# MT-CHARHER_V1_0_0.net
KiCad netlist of a schematic drawn in Altium Designer
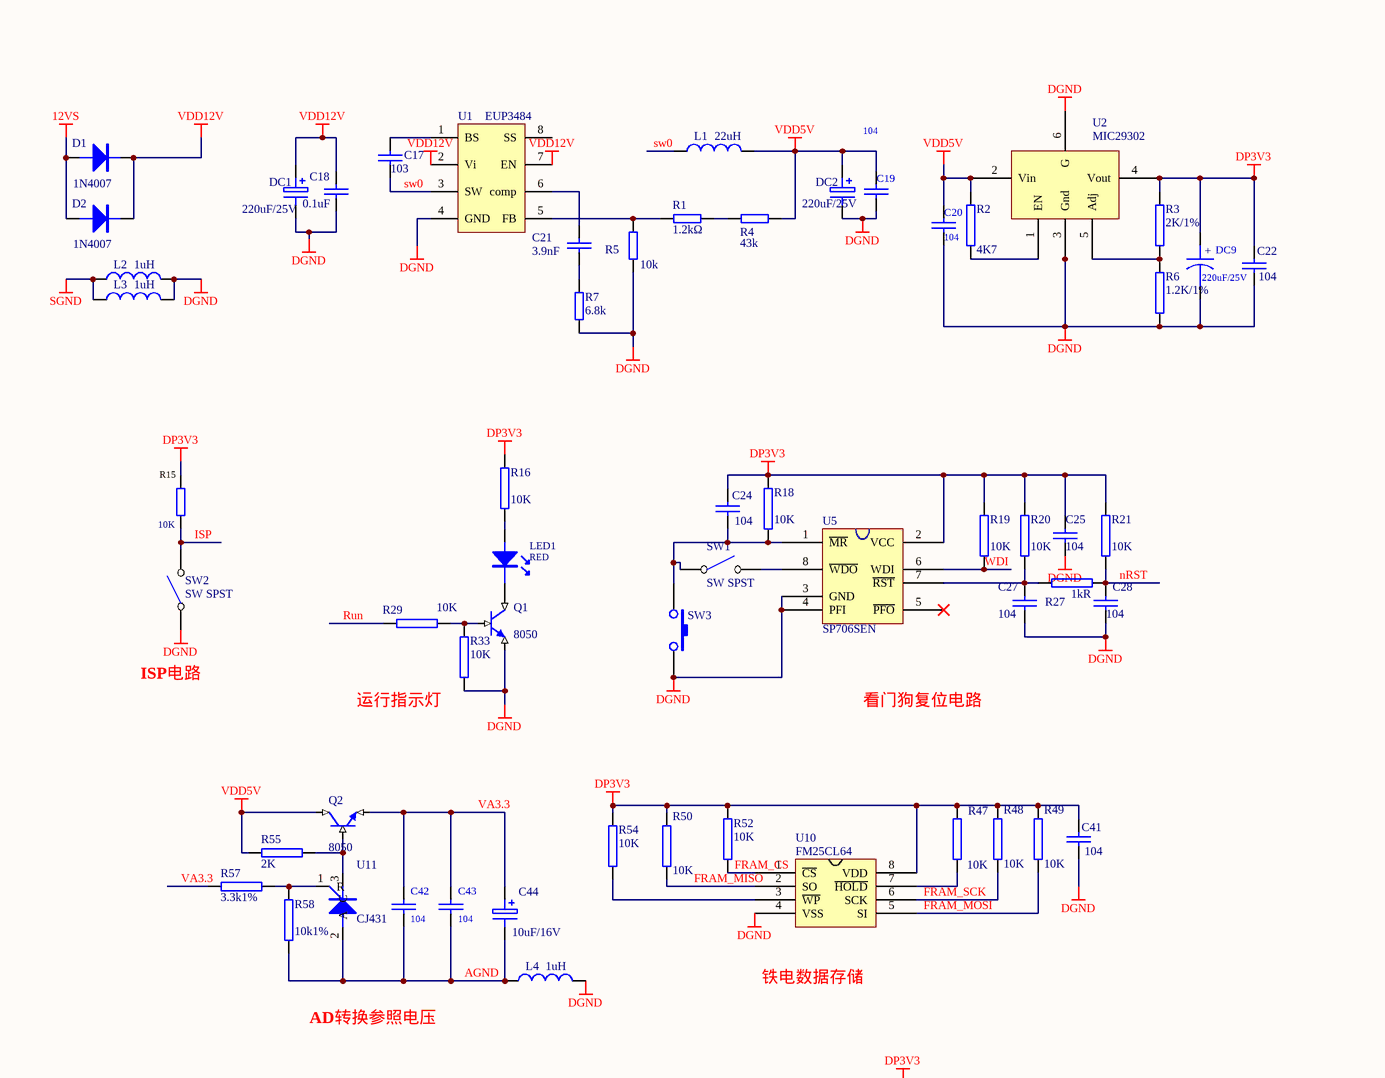
[diagram p0: MT-CHARHER  V1.0.0.SchDoc, top left]
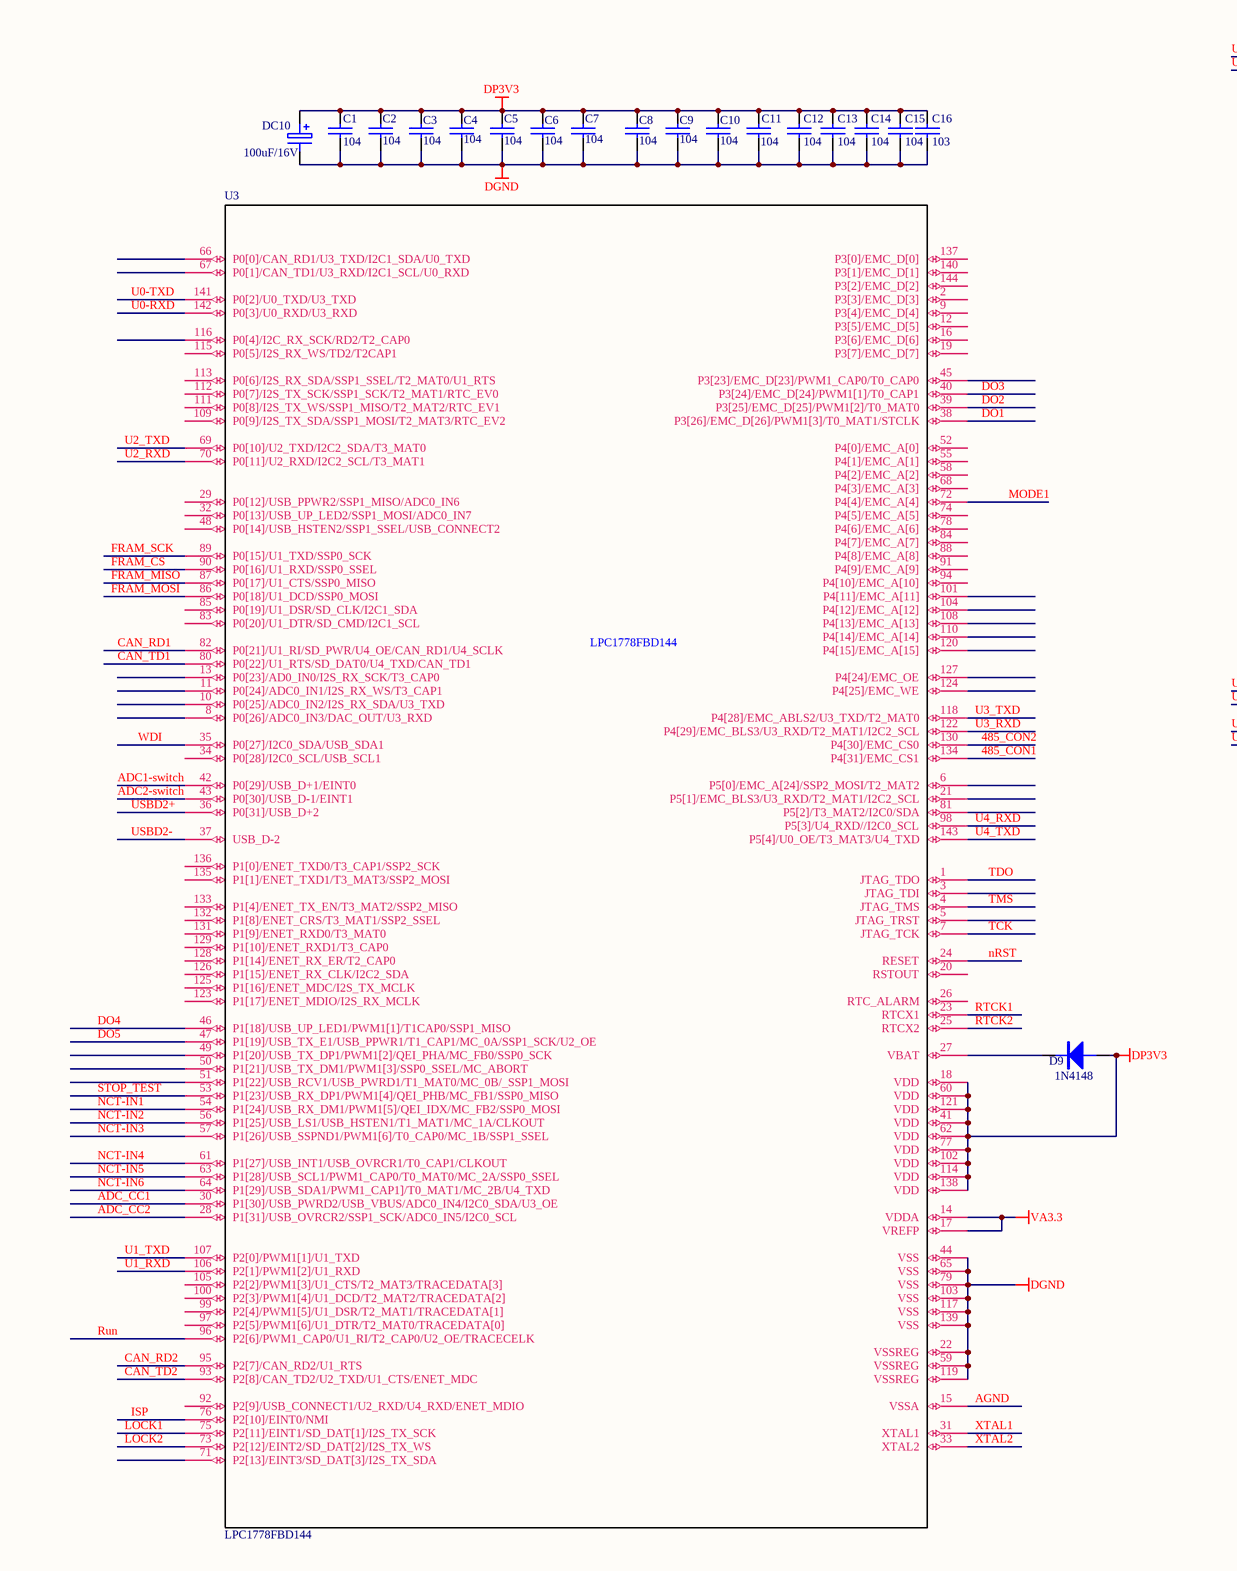
[diagram p1: MT-CHARHER  V1.0.0.SchDoc, top middle]
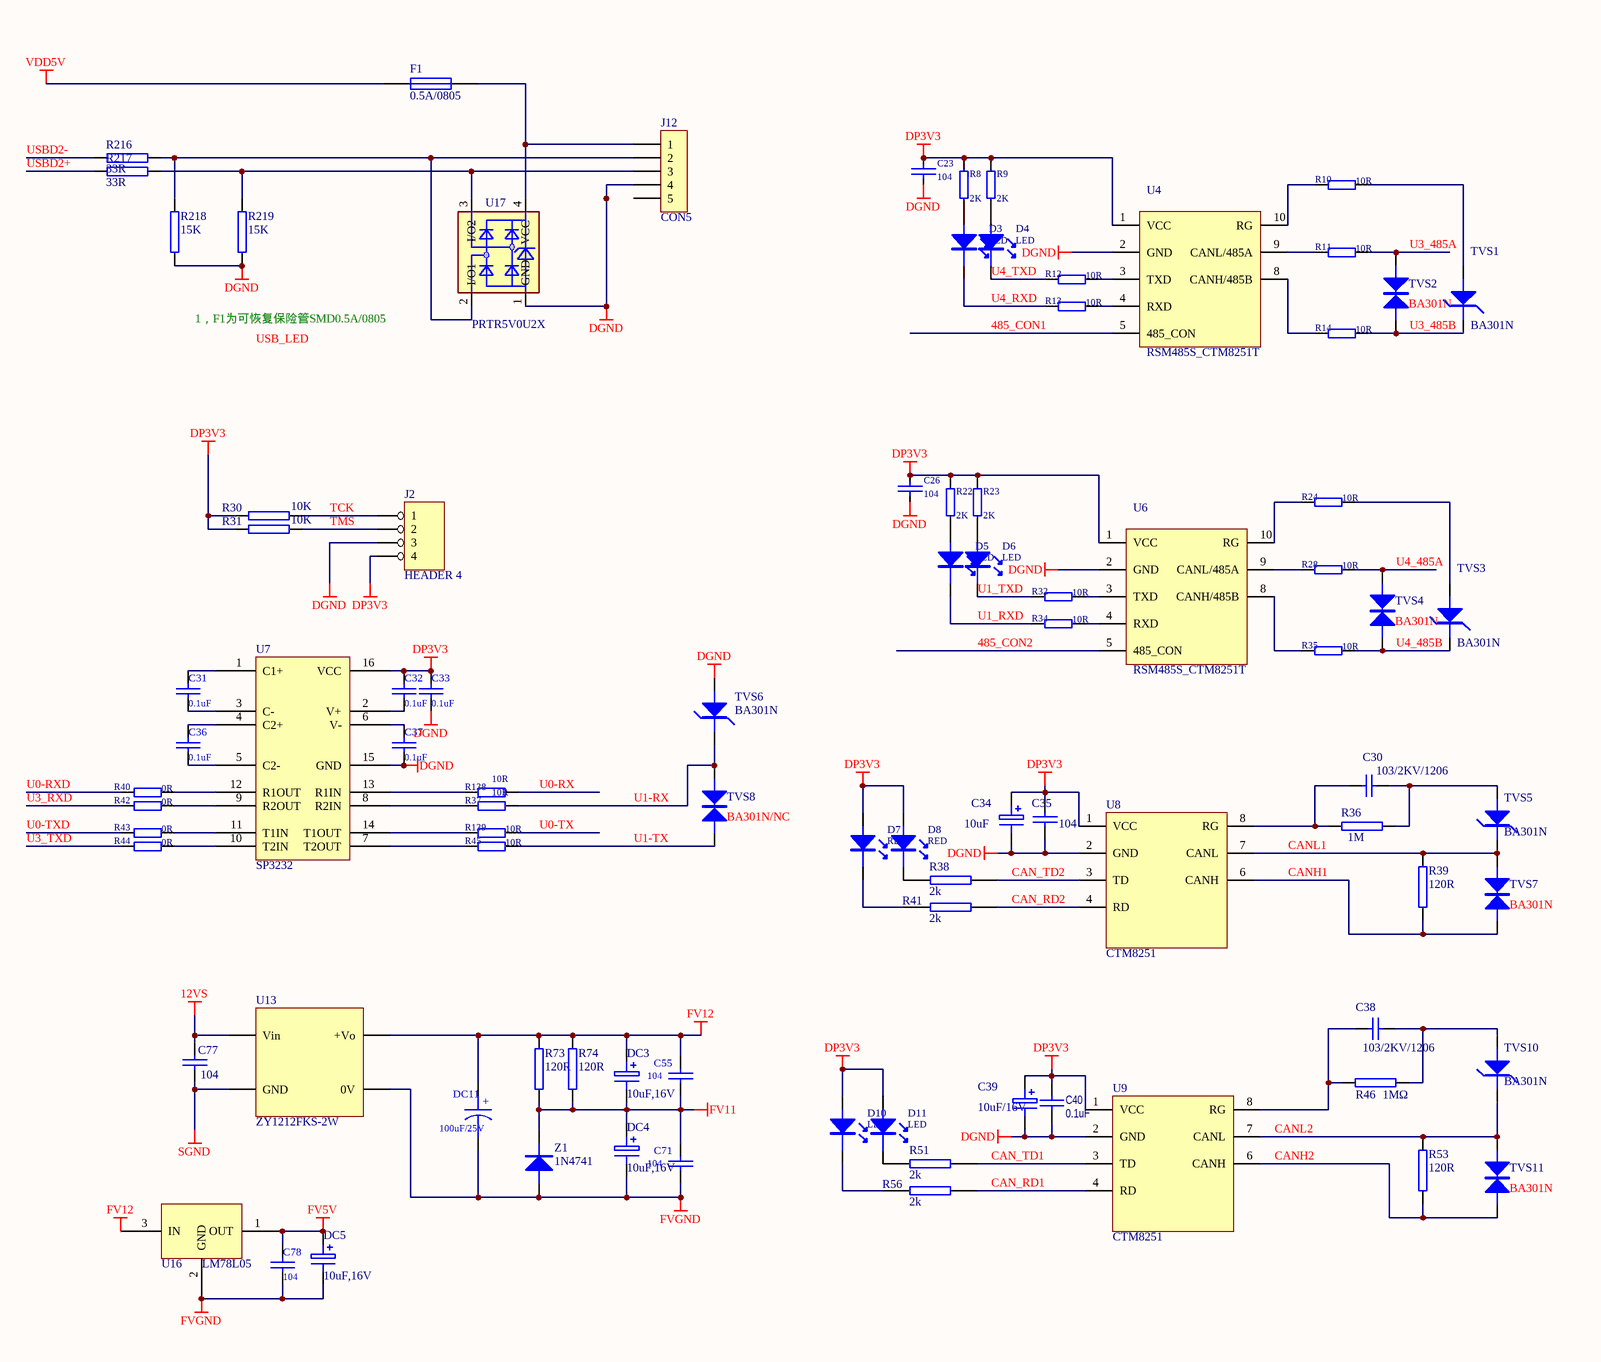
[diagram p2: MT-CHARHER  V1.0.0.SchDoc, top right]
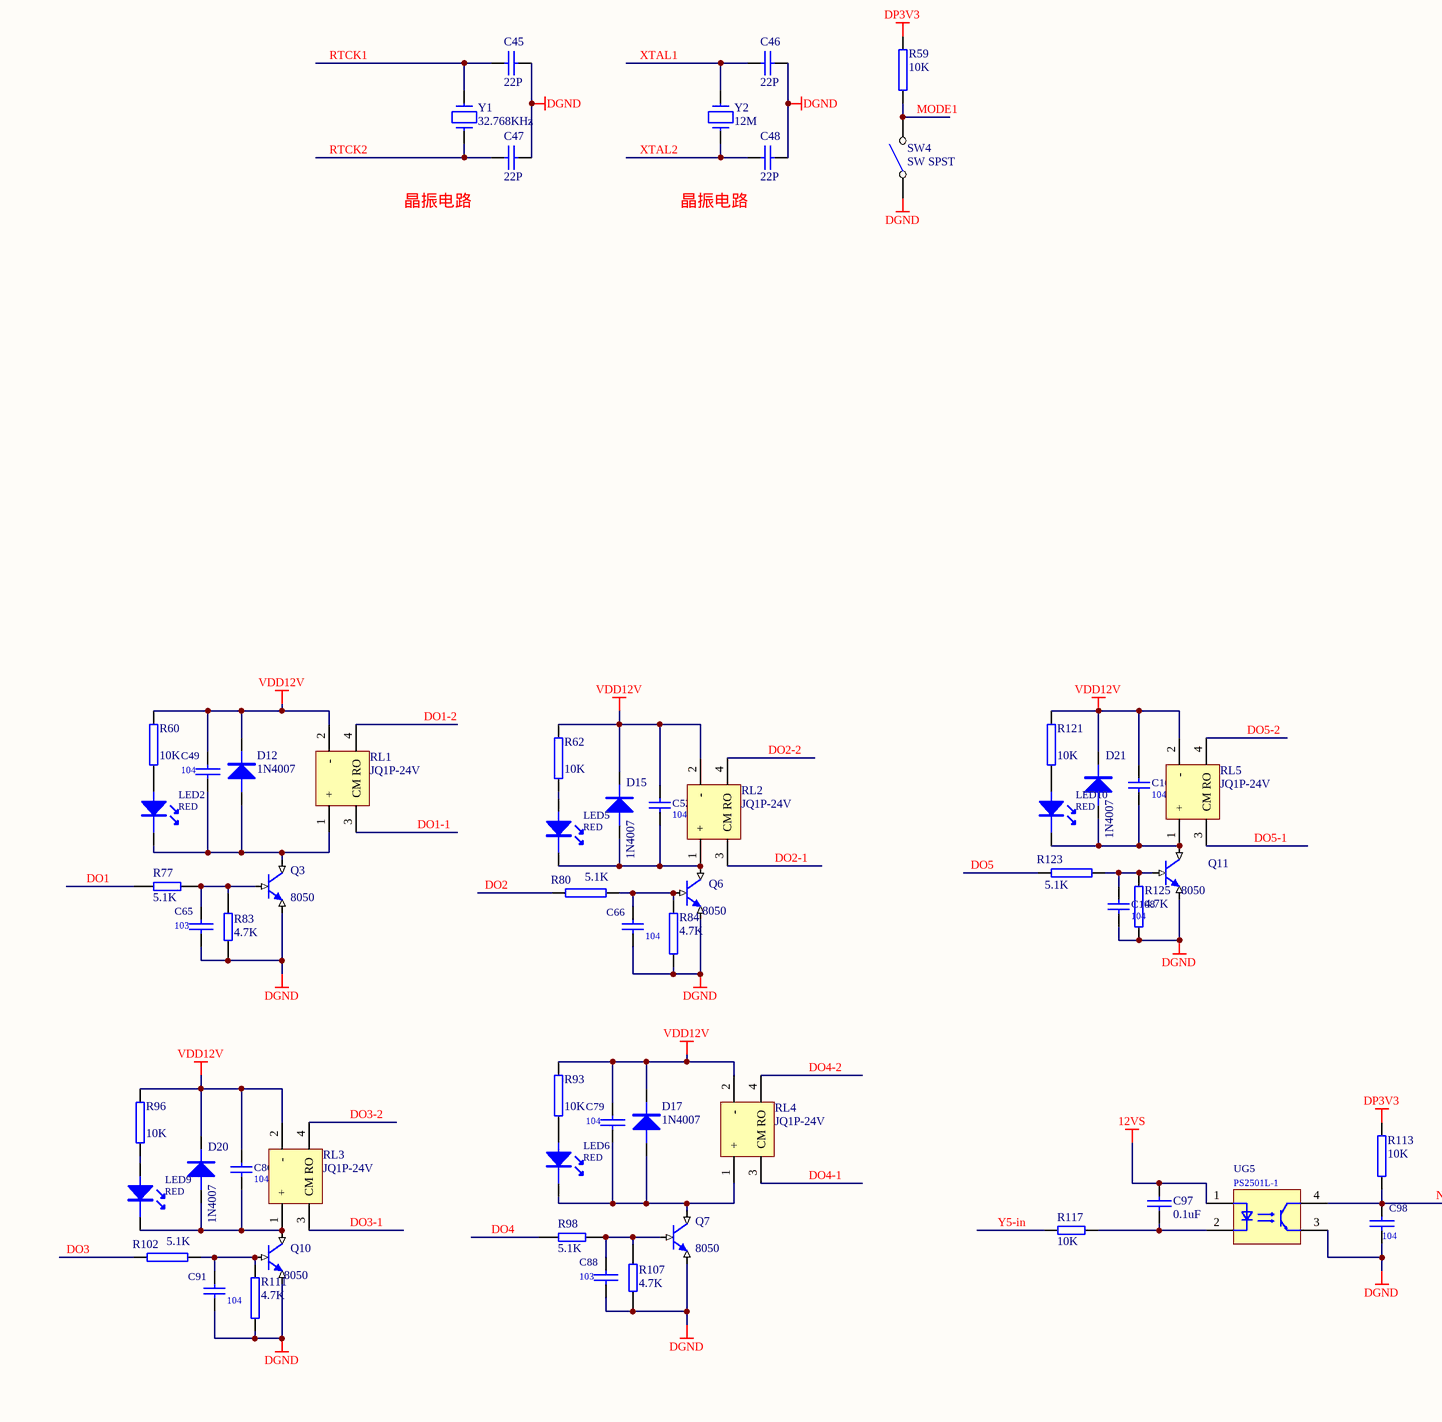
[diagram p3: MT-CHARHER  V1.0.0.SchDoc, bottom left]
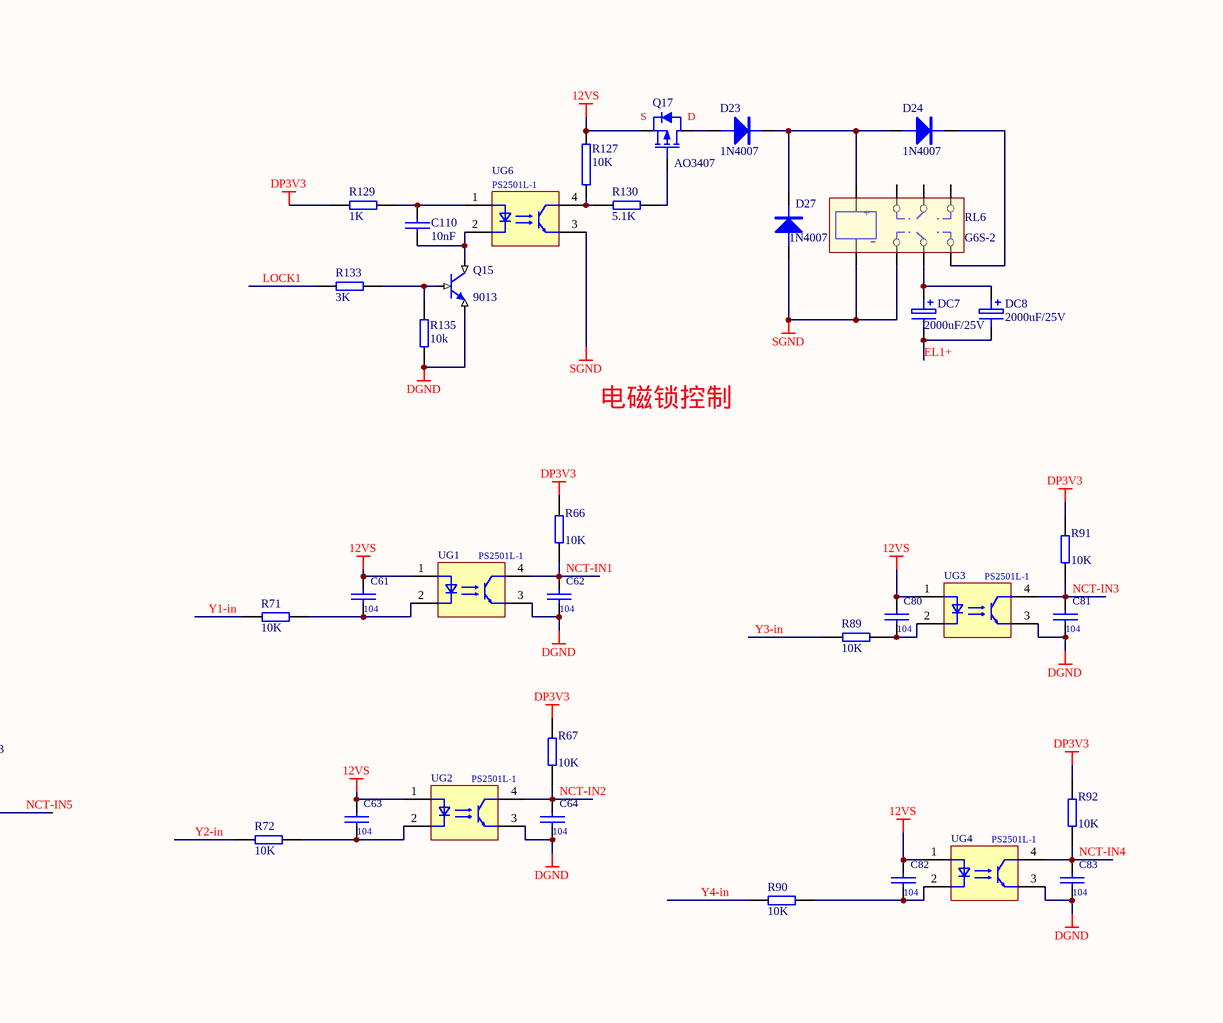
[diagram p4: MT-CHARHER  V1.0.0.SchDoc, bottom middle]
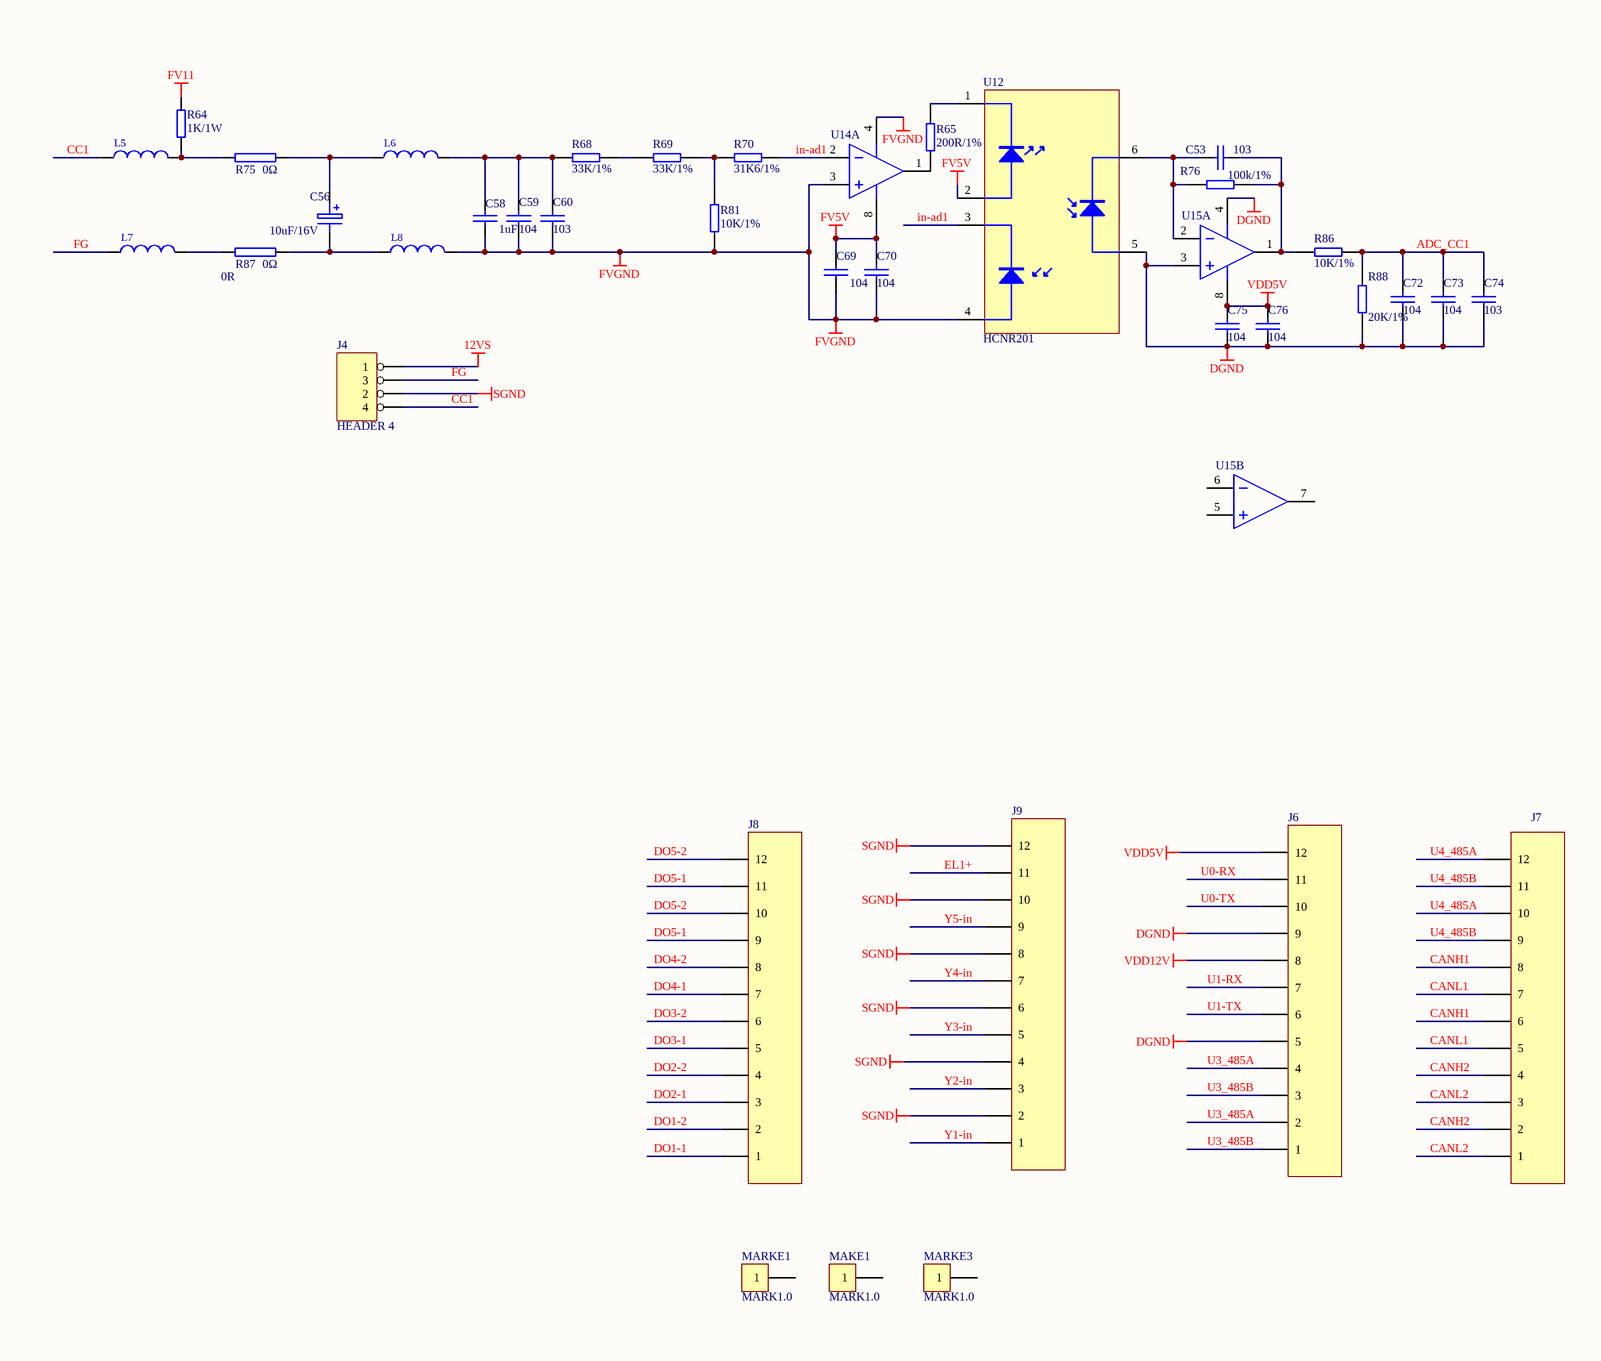
[diagram p5: MT-CHARHER  V1.0.0.SchDoc, bottom right]

(export (version "E")
  (design (tool "Eeschema 10.0.6"))
  (components
    (comp (ref "C1") (value "104") (footprint "0603C") (libsource (lib "*") (part "CAP1")))
    (comp (ref "C2") (value "104") (footprint "0603C") (libsource (lib "*") (part "CAP1")))
    (comp (ref "C3") (value "104") (footprint "0603C") (libsource (lib "*") (part "CAP1")))
    (comp (ref "C4") (value "104") (footprint "0603C") (libsource (lib "*") (part "CAP1")))
    (comp (ref "C5") (value "104") (footprint "0603C") (libsource (lib "*") (part "CAP1")))
    (comp (ref "C6") (value "104") (footprint "0603C") (libsource (lib "*") (part "CAP1")))
    (comp (ref "C7") (value "104") (footprint "0603C") (libsource (lib "*") (part "CAP1")))
    (comp (ref "C8") (value "104") (footprint "0603C") (libsource (lib "*") (part "CAP1")))
    (comp (ref "C9") (value "104") (footprint "0603C") (libsource (lib "*") (part "CAP1")))
    (comp (ref "C10") (value "104") (footprint "0603C") (libsource (lib "*") (part "CAP1")))
    (comp (ref "C11") (value "104") (footprint "0603C") (libsource (lib "*") (part "CAP1")))
    (comp (ref "C12") (value "104") (footprint "0603C") (libsource (lib "") (part "CAP1_2")))
    (comp (ref "C13") (value "104") (footprint "0603C") (libsource (lib "*") (part "CAP1")))
    (comp (ref "C14") (value "104") (footprint "0603C") (libsource (lib "*") (part "CAP1")))
    (comp (ref "C15") (value "104") (footprint "0603C") (libsource (lib "*") (part "CAP1")))
    (comp (ref "C16") (value "103") (footprint "0603C") (libsource (lib "*") (part "CAP1")))
    (comp (ref "C17") (value "103") (footprint "0603C") (libsource (lib "*") (part "CAP")))
    (comp (ref "C18") (value "0.1uF") (footprint "0805C") (libsource (lib "*") (part "CAP")))
    (comp (ref "C19")
      (value "104")
      (footprint "0603C")
      (description "Capacitor")
      (libsource (lib "*") (part "CAP"))
    )
    (comp (ref "C20")
      (value "104")
      (footprint "0603C")
      (description "Capacitor")
      (libsource (lib "*") (part "CAP"))
    )
    (comp (ref "C21") (value "3.9nF") (footprint "0603C") (libsource (lib "*") (part "CAP")))
    (comp (ref "C22")
      (value "104")
      (footprint "0603C")
      (description "CAP")
      (libsource (lib "*") (part "CAP1"))
    )
    (comp (ref "C23") (value "104") (footprint "0603C") (libsource (lib "*") (part "CAP_1")))
    (comp (ref "C24")
      (value "104")
      (footprint "0603C")
      (description "CAP")
      (libsource (lib "*") (part "CAP1"))
    )
    (comp (ref "C25")
      (value "104")
      (footprint "0603C")
      (description "CAP")
      (libsource (lib "*") (part "CAP1"))
    )
    (comp (ref "C26") (value "104") (footprint "0603C") (libsource (lib "*") (part "CAP_1")))
    (comp (ref "C27")
      (value "104")
      (footprint "0603C")
      (description "CAP")
      (libsource (lib "*") (part "CAP1"))
    )
    (comp (ref "C28")
      (value "104")
      (footprint "0603C")
      (description "CAP")
      (libsource (lib "*") (part "CAP1"))
    )
    (comp (ref "C30")
      (value "103/2KV/1206")
      (footprint "1206C")
      (description "C0603")
      (fields (field (name "PUBLISHER") "*"))
      (libsource (lib "*") (part "0.1uF"))
    )
    (comp (ref "C31")
      (value "0.1uF")
      (footprint "0603C")
      (description "Capacitor")
      (libsource (lib "*") (part "CAP"))
    )
    (comp (ref "C32")
      (value "0.1uF")
      (footprint "0603C")
      (description "Capacitor")
      (libsource (lib "*") (part "CAP"))
    )
    (comp (ref "C33")
      (value "0.1uF")
      (footprint "0603C")
      (description "Capacitor")
      (libsource (lib "*") (part "CAP"))
    )
    (comp (ref "C34") (value "10uF") (footprint "CA1206") (libsource (lib "*") (part "CAP2")))
    (comp (ref "C35")
      (value "104")
      (footprint "0603C")
      (description "Capacitor")
      (libsource (lib "*") (part "CAP"))
    )
    (comp (ref "C36")
      (value "0.1uF")
      (footprint "0603C")
      (description "Capacitor")
      (libsource (lib "*") (part "CAP"))
    )
    (comp (ref "C37")
      (value "0.1uF")
      (footprint "0603C")
      (description "Capacitor")
      (libsource (lib "*") (part "CAP"))
    )
    (comp (ref "C38")
      (value "103/2KV/1206")
      (footprint "1206C")
      (description "C0603")
      (fields (field (name "PUBLISHER") "*"))
      (libsource (lib "*") (part "0.1uF"))
    )
    (comp (ref "C39") (value "10uF/16V") (footprint "CA1206") (libsource (lib "*") (part "CAP2")))
    (comp (ref "C40")
      (value "0.1uF")
      (footprint "0603C")
      (description "Capacitor")
      (libsource (lib "*") (part "CAP"))
    )
    (comp (ref "C41") (value "104") (footprint "0603C") (libsource (lib "*") (part "CAP1")))
    (comp (ref "C42")
      (value "104")
      (footprint "0603C")
      (description "Capacitor")
      (libsource (lib "*") (part "CAP"))
    )
    (comp (ref "C43")
      (value "104")
      (footprint "0603C")
      (description "Capacitor")
      (libsource (lib "*") (part "CAP"))
    )
    (comp (ref "C44") (value "10uF/16V") (footprint "CA1206") (libsource (lib "*") (part "CAP2")))
    (comp (ref "C45") (value "22P") (footprint "0603C") (libsource (lib "*") (part "CAP1")))
    (comp (ref "C46") (value "22P") (footprint "0603C") (libsource (lib "*") (part "CAP1")))
    (comp (ref "C47") (value "22P") (footprint "0603C") (libsource (lib "*") (part "CAP1")))
    (comp (ref "C48") (value "22P") (footprint "0603C") (libsource (lib "*") (part "CAP1")))
    (comp (ref "C49")
      (value "104")
      (footprint "0603C")
      (description "Capacitor")
      (libsource (lib "*") (part "CAP"))
    )
    (comp (ref "C52")
      (value "104")
      (footprint "0603C")
      (description "Capacitor")
      (fields (field (name "PUBLISHER") "*"))
      (libsource (lib "*") (part "Cap"))
    )
    (comp (ref "C53")
      (value "103")
      (footprint "0603C")
      (description "Capacitor")
      (libsource (lib "") (part "CAP1_1"))
    )
    (comp (ref "C55")
      (value "104")
      (footprint "0805C")
      (description "Capacitor")
      (libsource (lib "*") (part "CAP"))
    )
    (comp (ref "C56") (value "10uF/16V") (footprint "CA1206") (libsource (lib "*") (part "CAP2")))
    (comp (ref "C58")
      (value "1uF")
      (footprint "0805C")
      (description "Capacitor")
      (libsource (lib "") (part "CAP_1"))
    )
    (comp (ref "C59")
      (value "104")
      (footprint "0603C")
      (description "Capacitor")
      (libsource (lib "") (part "CAP1_1"))
    )
    (comp (ref "C60")
      (value "103")
      (footprint "0603C")
      (description "Capacitor")
      (libsource (lib "") (part "CAP1_1"))
    )
    (comp (ref "C61")
      (value "104")
      (footprint "0603C")
      (description "Capacitor")
      (libsource (lib "*") (part "CAP"))
    )
    (comp (ref "C62")
      (value "104")
      (footprint "0603C")
      (description "Capacitor")
      (libsource (lib "*") (part "CAP"))
    )
    (comp (ref "C63")
      (value "104")
      (footprint "0603C")
      (description "Capacitor")
      (libsource (lib "*") (part "CAP"))
    )
    (comp (ref "C64")
      (value "104")
      (footprint "0603C")
      (description "Capacitor")
      (libsource (lib "*") (part "CAP"))
    )
    (comp (ref "C65")
      (value "103")
      (footprint "0603C")
      (description "Capacitor")
      (libsource (lib "*") (part "CAP"))
    )
    (comp (ref "C66")
      (value "104")
      (footprint "0603C")
      (description "Capacitor")
      (fields (field (name "PUBLISHER") "*"))
      (libsource (lib "*") (part "Cap"))
    )
    (comp (ref "C69")
      (value "104")
      (footprint "0603C")
      (description "Capacitor")
      (libsource (lib "") (part "CAP1_1"))
    )
    (comp (ref "C70")
      (value "104")
      (footprint "0603C")
      (description "Capacitor")
      (libsource (lib "") (part "CAP1_1"))
    )
    (comp (ref "C71")
      (value "104")
      (footprint "0805C")
      (description "Capacitor")
      (libsource (lib "*") (part "CAP"))
    )
    (comp (ref "C72")
      (value "104")
      (footprint "0603C")
      (description "Capacitor")
      (libsource (lib "") (part "CAP1_1"))
    )
    (comp (ref "C73")
      (value "104")
      (footprint "0603C")
      (description "Capacitor")
      (libsource (lib "") (part "CAP1_1"))
    )
    (comp (ref "C74")
      (value "103")
      (footprint "0603C")
      (description "Capacitor")
      (libsource (lib "") (part "CAP1_1"))
    )
    (comp (ref "C75")
      (value "104")
      (footprint "0603C")
      (description "Capacitor")
      (libsource (lib "") (part "CAP1_1"))
    )
    (comp (ref "C76")
      (value "104")
      (footprint "0603C")
      (description "Capacitor")
      (libsource (lib "") (part "CAP1_1"))
    )
    (comp (ref "C77") (value "104") (footprint "0805C") (libsource (lib "*") (part "CAP1")))
    (comp (ref "C78")
      (value "104")
      (footprint "0805C")
      (description "Capacitor")
      (libsource (lib "*") (part "CAP"))
    )
    (comp (ref "C79")
      (value "104")
      (footprint "0603C")
      (description "Capacitor")
      (libsource (lib "*") (part "CAP"))
    )
    (comp (ref "C80")
      (value "104")
      (footprint "0603C")
      (description "Capacitor")
      (libsource (lib "*") (part "CAP"))
    )
    (comp (ref "C81")
      (value "104")
      (footprint "0603C")
      (description "Capacitor")
      (libsource (lib "*") (part "CAP"))
    )
    (comp (ref "C82")
      (value "104")
      (footprint "0603C")
      (description "Capacitor")
      (libsource (lib "*") (part "CAP"))
    )
    (comp (ref "C83")
      (value "104")
      (footprint "0603C")
      (description "Capacitor")
      (libsource (lib "*") (part "CAP"))
    )
    (comp (ref "C86")
      (value "104")
      (footprint "0603C")
      (description "Capacitor")
      (fields (field (name "PUBLISHER") "*"))
      (libsource (lib "*") (part "Cap"))
    )
    (comp (ref "C88")
      (value "103")
      (footprint "0603C")
      (description "Capacitor")
      (libsource (lib "*") (part "CAP"))
    )
    (comp (ref "C91")
      (value "104")
      (footprint "0603C")
      (description "Capacitor")
      (fields (field (name "PUBLISHER") "*"))
      (libsource (lib "*") (part "Cap"))
    )
    (comp (ref "C97")
      (value "0.1uF")
      (footprint "0603C")
      (description "Capacitor")
      (libsource (lib "*") (part "CAP"))
    )
    (comp (ref "C98")
      (value "104")
      (footprint "0603C")
      (description "Capacitor")
      (libsource (lib "*") (part "CAP"))
    )
    (comp (ref "C106")
      (value "104")
      (footprint "0603C")
      (description "Capacitor")
      (fields (field (name "PUBLISHER") "*"))
      (libsource (lib "*") (part "Cap"))
    )
    (comp (ref "C108")
      (value "104")
      (footprint "0603C")
      (description "Capacitor")
      (fields (field (name "PUBLISHER") "*"))
      (libsource (lib "*") (part "Cap"))
    )
    (comp (ref "C110")
      (value "10nF")
      (footprint "0603C")
      (description "Capacitor")
      (libsource (lib "*") (part "CAP"))
    )
    (comp (ref "D1") (value "1N4007") (footprint "1206D") (libsource (lib "*") (part "DIODE")))
    (comp (ref "D2") (value "1N4007") (footprint "1206D") (libsource (lib "*") (part "DIODE")))
    (comp (ref "D3") (value "LED") (footprint "D0805") (libsource (lib "*") (part "LED")))
    (comp (ref "D4") (value "LED") (footprint "D0805") (libsource (lib "*") (part "LED")))
    (comp (ref "D5") (value "LED") (footprint "D0805") (libsource (lib "*") (part "LED")))
    (comp (ref "D6") (value "LED") (footprint "D0805") (libsource (lib "*") (part "LED")))
    (comp (ref "D7") (value "RED") (footprint "D0805") (libsource (lib "*") (part "LED")))
    (comp (ref "D8") (value "RED") (footprint "D0805") (libsource (lib "*") (part "LED")))
    (comp (ref "D9") (value "1N4148") (footprint "1206D") (libsource (lib "*") (part "DIODE")))
    (comp (ref "D10") (value "LED") (footprint "D0805") (libsource (lib "*") (part "LED")))
    (comp (ref "D11") (value "LED") (footprint "D0805") (libsource (lib "*") (part "LED")))
    (comp (ref "D12") (value "1N4007") (footprint "1206D") (libsource (lib "*") (part "DIODE")))
    (comp (ref "D15") (value "1N4007") (footprint "1206D") (libsource (lib "*") (part "DIODE")))
    (comp (ref "D17") (value "1N4007") (footprint "1206D") (libsource (lib "*") (part "DIODE")))
    (comp (ref "D20") (value "1N4007") (footprint "1206D") (libsource (lib "*") (part "DIODE")))
    (comp (ref "D21") (value "1N4007") (footprint "1206D") (libsource (lib "*") (part "DIODE")))
    (comp (ref "D23") (value "1N4007") (footprint "1206D") (libsource (lib "*") (part "DIODE")))
    (comp (ref "D24") (value "1N4007") (footprint "1206D") (libsource (lib "*") (part "DIODE")))
    (comp (ref "D27") (value "1N4007") (footprint "1206D") (libsource (lib "*") (part "DIODE")))
    (comp (ref "DC1") (value "220uF/25V") (footprint "C100UF16VEJ") (libsource (lib "*") (part "CAP2")))
    (comp (ref "DC2") (value "220uF/25V") (footprint "C100UF16VEJ") (libsource (lib "*") (part "CAP2")))
    (comp (ref "DC3") (value "10uF,16V") (footprint "CA1206") (libsource (lib "*") (part "CAP2")))
    (comp (ref "DC4") (value "10uF,16V") (footprint "CA1206") (libsource (lib "*") (part "CAP2")))
    (comp (ref "DC5") (value "10uF,16V") (footprint "CA1206") (libsource (lib "*") (part "CAP2")))
    (comp (ref "DC7") (value "2000uF/25V") (footprint "CAP12.5*20") (libsource (lib "SCH") (part "CAP2")))
    (comp (ref "DC8") (value "2000uF/25V") (footprint "CAP12.5*20") (libsource (lib "SCH") (part "CAP2")))
    (comp (ref "DC9")
      (value "220uF/25V")
      (footprint "C100UF16VEJ")
      (description "Capacitor")
      (libsource (lib "*") (part "CAPACITOR POL"))
    )
    (comp (ref "DC10") (value "100uF/16V") (footprint "C100UF16VEJ") (libsource (lib "*") (part "CAP2")))
    (comp (ref "DC11")
      (value "100uF/25V")
      (footprint "C100UF16VEJ")
      (description "Capacitor")
      (libsource (lib "*") (part "CAPACITOR POL"))
    )
    (comp (ref "F1")
      (value "0.5A/0805")
      (footprint "0805R")
      (description "Fuse")
      (libsource (lib "EasyCortex M3-1752") (part "FUSE1"))
    )
    (comp (ref "J2")
      (value "HEADER 4")
      (footprint "COM-2.54mm-90")
      (description "4 Pin Header")
      (libsource (lib "ucharge06011415") (part "4 HEADER"))
    )
    (comp (ref "J4")
      (value "HEADER 4")
      (footprint "KF2EDG-4P-3.81mm")
      (description "4 Pin Header")
      (libsource (lib "ueee20160531") (part "4 HEADER"))
    )
    (comp (ref "J6")
      (value "J?")
      (footprint "KF2EDG-12P-3.81mm")
      (libsource (lib "UEEE20160408") (part "CON12"))
    )
    (comp (ref "J7")
      (value "J?")
      (footprint "KF2EDG-12P-3.81mm")
      (libsource (lib "UEEE20160408") (part "CON12"))
    )
    (comp (ref "J8")
      (value "J8")
      (footprint "KF2EDG-12P-3.81mm")
      (libsource (lib "UEEE20160408") (part "CON12"))
    )
    (comp (ref "J9")
      (value "J8")
      (footprint "KF2EDG-12P-3.81mm")
      (libsource (lib "UEEE20160408") (part "CON12"))
    )
    (comp (ref "J12")
      (value "CON5")
      (footprint "USB-A")
      (description "Connector")
      (libsource (lib "*") (part "CON5"))
    )
    (comp (ref "L1") (value "22uH") (footprint "LC7*7*3_L") (libsource (lib "*") (part "INDUCTOR")))
    (comp (ref "L2") (value "1uH") (footprint "1206R") (libsource (lib "*") (part "INDUCTOR")))
    (comp (ref "L3") (value "1uH") (footprint "1206R") (libsource (lib "*") (part "INDUCTOR")))
    (comp (ref "L4") (value "1uH") (footprint "1206R") (libsource (lib "*") (part "INDUCTOR")))
    (comp (ref "L5") (value "1uH") (footprint "LC7*7*3_L") (libsource (lib "*") (part "INDUCTOR")))
    (comp (ref "L6") (value "1uH") (footprint "1206R") (libsource (lib "*") (part "INDUCTOR")))
    (comp (ref "L7") (value "1uH") (footprint "LC7*7*3_L") (libsource (lib "*") (part "INDUCTOR")))
    (comp (ref "L8") (value "1uH") (footprint "1206R") (libsource (lib "*") (part "INDUCTOR")))
    (comp (ref "LED1") (value "RED") (footprint "D0805") (libsource (lib "*") (part "LED")))
    (comp (ref "LED2") (value "RED") (footprint "D0805") (libsource (lib "*") (part "LED")))
    (comp (ref "LED5") (value "RED") (footprint "D0805") (libsource (lib "*") (part "LED")))
    (comp (ref "LED6") (value "RED") (footprint "D0805") (libsource (lib "*") (part "LED")))
    (comp (ref "LED9") (value "RED") (footprint "D0805") (libsource (lib "*") (part "LED")))
    (comp (ref "LED10") (value "RED") (footprint "D0805") (libsource (lib "*") (part "LED")))
    (comp (ref "MAKE1")
      (value "MARK1.0")
      (footprint "MARK1.0")
      (description "Connector")
      (libsource (lib "*") (part "CON1"))
    )
    (comp (ref "MARKE1")
      (value "MARK1.0")
      (footprint "MARK1.0")
      (description "Connector")
      (libsource (lib "*") (part "CON1"))
    )
    (comp (ref "MARKE3")
      (value "MARK1.0")
      (footprint "MARK1.0")
      (description "Connector")
      (libsource (lib "*") (part "CON1"))
    )
    (comp (ref "Q1") (value "8050") (footprint "SOT23") (libsource (lib "*") (part "NPN")))
    (comp (ref "Q2") (value "8050") (footprint "SOT23") (libsource (lib "*") (part "NPN")))
    (comp (ref "Q3") (value "8050") (footprint "SOT23") (libsource (lib "*") (part "NPN")))
    (comp (ref "Q6") (value "8050") (footprint "SOT23") (libsource (lib "*") (part "NPN")))
    (comp (ref "Q7") (value "8050") (footprint "SOT23") (libsource (lib "*") (part "NPN")))
    (comp (ref "Q10") (value "8050") (footprint "SOT23") (libsource (lib "*") (part "NPN")))
    (comp (ref "Q11") (value "8050") (footprint "SOT23") (libsource (lib "*") (part "NPN")))
    (comp (ref "Q15") (value "9013") (footprint "SOT23") (libsource (lib "*") (part "NPN")))
    (comp (ref "Q17") (value "AO3407") (footprint "SOT-23L") (libsource (lib "SCH") (part "PMOS")))
    (comp (ref "R1") (value "1.2kΩ") (footprint "0603R") (libsource (lib "*") (part "R_S")))
    (comp (ref "R2") (value "4K7") (footprint "0603R") (libsource (lib "") (part "RES1_1")))
    (comp (ref "R3") (value "2K/1%") (footprint "0603R") (libsource (lib "") (part "RES1_1")))
    (comp (ref "R4") (value "43k") (footprint "0603R") (libsource (lib "*") (part "R_S")))
    (comp (ref "R5") (value "10k") (footprint "0603R") (libsource (lib "*") (part "R_S")))
    (comp (ref "R6") (value "1.2K/1%") (footprint "0603R") (libsource (lib "") (part "RES1_1")))
    (comp (ref "R7") (value "6.8k") (footprint "0603R") (libsource (lib "*") (part "R_S")))
    (comp (ref "R8")
      (value "2K")
      (footprint "0603R")
      (description "RES")
      (libsource (lib "*") (part "RES-1"))
    )
    (comp (ref "R9")
      (value "2K")
      (footprint "0603R")
      (description "RES")
      (libsource (lib "*") (part "RES-1"))
    )
    (comp (ref "R10")
      (value "10R")
      (footprint "0603R")
      (description "RES")
      (libsource (lib "*") (part "RES-1"))
    )
    (comp (ref "R11")
      (value "10R")
      (footprint "0603R")
      (description "RES")
      (libsource (lib "*") (part "RES-1"))
    )
    (comp (ref "R12")
      (value "10R")
      (footprint "0603R")
      (description "RES")
      (libsource (lib "*") (part "RES-1"))
    )
    (comp (ref "R13")
      (value "10R")
      (footprint "0603R")
      (description "RES")
      (libsource (lib "*") (part "RES-1"))
    )
    (comp (ref "R14")
      (value "10R")
      (footprint "0603R")
      (description "RES")
      (libsource (lib "*") (part "RES-1"))
    )
    (comp (ref "R15")
      (value "10K")
      (footprint "0603R")
      (description "RES")
      (libsource (lib "*") (part "RES-1"))
    )
    (comp (ref "R16") (value "10K") (footprint "0603R") (libsource (lib "") (part "RES1_1")))
    (comp (ref "R18") (value "10K") (footprint "0603R") (libsource (lib "") (part "RES1_1")))
    (comp (ref "R19") (value "10K") (footprint "0603R") (libsource (lib "") (part "RES1_1")))
    (comp (ref "R20") (value "10K") (footprint "0603R") (libsource (lib "") (part "RES1_1")))
    (comp (ref "R21") (value "10K") (footprint "0603R") (libsource (lib "") (part "RES1_1")))
    (comp (ref "R22")
      (value "2K")
      (footprint "0603R")
      (description "RES")
      (libsource (lib "*") (part "RES-1"))
    )
    (comp (ref "R23")
      (value "2K")
      (footprint "0603R")
      (description "RES")
      (libsource (lib "*") (part "RES-1"))
    )
    (comp (ref "R24")
      (value "10R")
      (footprint "0603R")
      (description "RES")
      (libsource (lib "*") (part "RES-1"))
    )
    (comp (ref "R27") (value "1kR") (footprint "0603R") (libsource (lib "") (part "RES1_1")))
    (comp (ref "R28")
      (value "10R")
      (footprint "0603R")
      (description "RES")
      (libsource (lib "*") (part "RES-1"))
    )
    (comp (ref "R29") (value "10K") (footprint "0603R") (libsource (lib "") (part "RES1_1")))
    (comp (ref "R30") (value "10K") (footprint "0603R") (libsource (lib "") (part "RES1_1")))
    (comp (ref "R31") (value "10K") (footprint "0603R") (libsource (lib "") (part "RES1_1")))
    (comp (ref "R32")
      (value "10R")
      (footprint "0603R")
      (description "RES")
      (libsource (lib "*") (part "RES-1"))
    )
    (comp (ref "R33") (value "10K") (footprint "0603R") (libsource (lib "") (part "RES1_1")))
    (comp (ref "R34")
      (value "10R")
      (footprint "0603R")
      (description "RES")
      (libsource (lib "*") (part "RES-1"))
    )
    (comp (ref "R35")
      (value "10R")
      (footprint "0603R")
      (description "RES")
      (libsource (lib "*") (part "RES-1"))
    )
    (comp (ref "R36") (value "1M") (footprint "1206R") (libsource (lib "*") (part "RES2")))
    (comp (ref "R37")
      (value "10R")
      (footprint "0603R")
      (description "RES")
      (libsource (lib "*") (part "RES-1"))
    )
    (comp (ref "R38") (value "2k") (footprint "0603R") (libsource (lib "") (part "RES2_1")))
    (comp (ref "R39") (value "120R") (footprint "1206R") (libsource (lib "*") (part "RES2")))
    (comp (ref "R40")
      (value "0R")
      (footprint "0603R")
      (description "RES")
      (libsource (lib "*") (part "RES-1"))
    )
    (comp (ref "R41") (value "2k") (footprint "0603R") (libsource (lib "") (part "RES2_1")))
    (comp (ref "R42")
      (value "0R")
      (footprint "0603R")
      (description "RES")
      (libsource (lib "*") (part "RES-1"))
    )
    (comp (ref "R43")
      (value "0R")
      (footprint "0603R")
      (description "RES")
      (libsource (lib "*") (part "RES-1"))
    )
    (comp (ref "R44")
      (value "0R")
      (footprint "0603R")
      (description "RES")
      (libsource (lib "*") (part "RES-1"))
    )
    (comp (ref "R45")
      (value "10R")
      (footprint "0603R")
      (description "RES")
      (libsource (lib "*") (part "RES-1"))
    )
    (comp (ref "R46")
      (value "1MΩ")
      (footprint "1206R")
      (fields (field (name "Comment") "1M"))
      (libsource (lib "*") (part "RES2"))
    )
    (comp (ref "R47") (value "10K") (footprint "0603R") (libsource (lib "") (part "RES1_1")))
    (comp (ref "R48") (value "10K") (footprint "0603R") (libsource (lib "") (part "RES1_1")))
    (comp (ref "R49") (value "10K") (footprint "0603R") (libsource (lib "") (part "RES1_1")))
    (comp (ref "R50") (value "10K") (footprint "0603R") (libsource (lib "") (part "RES1_1")))
    (comp (ref "R51") (value "2k") (footprint "0603R") (libsource (lib "") (part "RES2_1")))
    (comp (ref "R52") (value "10K") (footprint "0603R") (libsource (lib "") (part "RES1_1")))
    (comp (ref "R53") (value "120R") (footprint "1206R") (libsource (lib "*") (part "RES2")))
    (comp (ref "R54") (value "10K") (footprint "0603R") (libsource (lib "") (part "RES1_1")))
    (comp (ref "R55") (value "2K") (footprint "0603R") (libsource (lib "") (part "RES1_1")))
    (comp (ref "R56") (value "2k") (footprint "0603R") (libsource (lib "") (part "RES2_1")))
    (comp (ref "R57") (value "3.3k1%") (footprint "0603R") (libsource (lib "") (part "RES1_1")))
    (comp (ref "R58") (value "10k1%") (footprint "0603R") (libsource (lib "") (part "RES1_1")))
    (comp (ref "R59") (value "10K") (footprint "0603R") (libsource (lib "") (part "RES1_1")))
    (comp (ref "R60") (value "10K") (footprint "0603R") (libsource (lib "") (part "RES1_1")))
    (comp (ref "R62") (value "10K") (footprint "0603R") (libsource (lib "") (part "RES1_1")))
    (comp (ref "R64") (value "1K/1W") (footprint "R1-1") (libsource (lib "*") (part "R_S")))
    (comp (ref "R65") (value "200R/1%") (footprint "0603R") (libsource (lib "*") (part "RES1")))
    (comp (ref "R66") (value "10K") (footprint "0603R") (libsource (lib "*") (part "RES1")))
    (comp (ref "R67") (value "10K") (footprint "0603R") (libsource (lib "*") (part "RES1")))
    (comp (ref "R68") (value "33K/1%") (footprint "0603R") (libsource (lib "*") (part "RES1")))
    (comp (ref "R69") (value "33K/1%") (footprint "0603R") (libsource (lib "*") (part "RES1")))
    (comp (ref "R70") (value "31K6/1%") (footprint "0603R") (libsource (lib "*") (part "RES1")))
    (comp (ref "R71") (value "10K") (footprint "0603R") (libsource (lib "*") (part "RES1")))
    (comp (ref "R72") (value "10K") (footprint "0603R") (libsource (lib "*") (part "RES1")))
    (comp (ref "R73") (value "120R") (footprint "1206R") (libsource (lib "*") (part "RES2")))
    (comp (ref "R74") (value "120R") (footprint "1206R") (libsource (lib "*") (part "RES2")))
    (comp (ref "R75") (value "0Ω") (footprint "1206R") (libsource (lib "*") (part "RES2")))
    (comp (ref "R76") (value "100k/1%") (footprint "0603R") (libsource (lib "*") (part "RES1")))
    (comp (ref "R77") (value "5.1K") (footprint "0603R") (libsource (lib "*") (part "RES1")))
    (comp (ref "R80") (value "5.1K") (footprint "0603R") (libsource (lib "") (part "RES1_1")))
    (comp (ref "R81") (value "10K/1%") (footprint "0603R") (libsource (lib "*") (part "RES1")))
    (comp (ref "R83") (value "4.7K") (footprint "0603R") (libsource (lib "*") (part "RES1")))
    (comp (ref "R84") (value "4.7K") (footprint "0603R") (libsource (lib "") (part "RES1_1")))
    (comp (ref "R86") (value "10K/1%") (footprint "0603R") (libsource (lib "*") (part "RES1")))
    (comp (ref "R87")
      (value "0R")
      (footprint "1206R")
      (fields (field (name "ALTIUM_VALUE") "0Ω"))
      (libsource (lib "*") (part "RES2"))
    )
    (comp (ref "R88") (value "20K/1%") (footprint "0603R") (libsource (lib "*") (part "RES1")))
    (comp (ref "R89") (value "10K") (footprint "0603R") (libsource (lib "*") (part "RES1")))
    (comp (ref "R90") (value "10K") (footprint "0603R") (libsource (lib "*") (part "RES1")))
    (comp (ref "R91") (value "10K") (footprint "0603R") (libsource (lib "*") (part "RES1")))
    (comp (ref "R92") (value "10K") (footprint "0603R") (libsource (lib "*") (part "RES1")))
    (comp (ref "R93") (value "10K") (footprint "0603R") (libsource (lib "") (part "RES1_1")))
    (comp (ref "R96") (value "10K") (footprint "0603R") (libsource (lib "") (part "RES1_1")))
    (comp (ref "R98") (value "5.1K") (footprint "0603R") (libsource (lib "*") (part "RES1")))
    (comp (ref "R102") (value "5.1K") (footprint "0603R") (libsource (lib "") (part "RES1_1")))
    (comp (ref "R107") (value "4.7K") (footprint "0603R") (libsource (lib "*") (part "RES1")))
    (comp (ref "R111") (value "4.7K") (footprint "0603R") (libsource (lib "") (part "RES1_1")))
    (comp (ref "R113") (value "10K") (footprint "0603R") (libsource (lib "") (part "RES1_1")))
    (comp (ref "R117")
      (value "10K")
      (footprint "0603R")
      (description "RES")
      (libsource (lib "*") (part "RES-1"))
    )
    (comp (ref "R121") (value "10K") (footprint "0603R") (libsource (lib "") (part "RES1_1")))
    (comp (ref "R123") (value "5.1K") (footprint "0603R") (libsource (lib "") (part "RES1_1")))
    (comp (ref "R125") (value "4.7K") (footprint "0603R") (libsource (lib "") (part "RES1_1")))
    (comp (ref "R127") (value "10K") (footprint "0603R") (libsource (lib "") (part "RES1_3")))
    (comp (ref "R129") (value "1K") (footprint "0603R") (libsource (lib "") (part "RES1_2")))
    (comp (ref "R130") (value "5.1K") (footprint "0603R") (libsource (lib "") (part "RES1_2")))
    (comp (ref "R133") (value "3K") (footprint "0603R") (libsource (lib "") (part "RES1_2")))
    (comp (ref "R135") (value "10k") (footprint "0603R") (libsource (lib "") (part "RES1_2")))
    (comp (ref "R138")
      (value "10R")
      (footprint "0603R")
      (description "RES")
      (libsource (lib "*") (part "RES-1"))
    )
    (comp (ref "R139")
      (value "10R")
      (footprint "0603R")
      (description "RES")
      (libsource (lib "*") (part "RES-1"))
    )
    (comp (ref "R216") (value "33R") (footprint "0603R") (libsource (lib "UEEE160329") (part "RES2")))
    (comp (ref "R217") (value "33R") (footprint "0603R") (libsource (lib "UEEE160329") (part "RES2")))
    (comp (ref "R218") (value "15K") (footprint "0603R") (libsource (lib "UEEE160329") (part "RES2")))
    (comp (ref "R219") (value "15K") (footprint "0603R") (libsource (lib "UEEE160329") (part "RES2")))
    (comp (ref "RL1")
      (value "JQ1P-24V")
      (footprint "HF32F-12V")
      (libsource (lib "UEEE20160408") (part "JQ1P-12V"))
    )
    (comp (ref "RL2")
      (value "JQ1P-24V")
      (footprint "HF32F-12V")
      (libsource (lib "UEEE20160408") (part "JQ1P-12V"))
    )
    (comp (ref "RL3")
      (value "JQ1P-24V")
      (footprint "HF32F-12V")
      (libsource (lib "UEEE20160408") (part "JQ1P-12V"))
    )
    (comp (ref "RL4")
      (value "JQ1P-24V")
      (footprint "HF32F-12V")
      (libsource (lib "UEEE20160408") (part "JQ1P-12V"))
    )
    (comp (ref "RL5")
      (value "JQ1P-24V")
      (footprint "HF32F-12V")
      (libsource (lib "UEEE20160408") (part "JQ1P-12V"))
    )
    (comp (ref "RL6") (value "G6S-2") (footprint "G6S-2") (libsource (lib "SCH") (part "G6S-2")))
    (comp (ref "SW1") (value "SW SPST") (footprint "SW1") (libsource (lib "*") (part "SW SPST")))
    (comp (ref "SW2") (value "SW SPST") (footprint "SW1") (libsource (lib "*") (part "SW SPST")))
    (comp (ref "SW3") (value "按键") (footprint "SW") (libsource (lib "*") (part "SW-PB")))
    (comp (ref "SW4") (value "SW SPST") (footprint "SW1") (libsource (lib "*") (part "SW SPST")))
    (comp (ref "TVS1") (value "BA301N") (footprint "3528TVS") (libsource (lib "*") (part "TVS-D")))
    (comp (ref "TVS2") (value "BA301N") (footprint "3528TVS") (libsource (lib "*") (part "TVS")))
    (comp (ref "TVS3") (value "BA301N") (footprint "3528TVS") (libsource (lib "*") (part "TVS-D")))
    (comp (ref "TVS4") (value "BA301N") (footprint "3528TVS") (libsource (lib "*") (part "TVS")))
    (comp (ref "TVS5") (value "BA301N") (footprint "3528TVS") (libsource (lib "*") (part "TVS-D")))
    (comp (ref "TVS6") (value "BA301N") (footprint "3528TVS") (libsource (lib "*") (part "TVS-D")))
    (comp (ref "TVS7") (value "BA301N") (footprint "3528TVS") (libsource (lib "*") (part "TVS")))
    (comp (ref "TVS8") (value "BA301N/NC") (footprint "3528TVS") (libsource (lib "*") (part "TVS")))
    (comp (ref "TVS10") (value "BA301N") (footprint "3528TVS") (libsource (lib "*") (part "TVS-D")))
    (comp (ref "TVS11") (value "BA301N") (footprint "3528TVS") (libsource (lib "*") (part "TVS")))
    (comp (ref "U1") (value "EUP3484") (footprint "SOP8") (libsource (lib "*") (part "EUP3484")))
    (comp (ref "U2") (value "MIC29302") (footprint "TO5B") (libsource (lib "*") (part "MIC29302")))
    (comp (ref "U3")
      (value "LPC1778FBD144")
      (footprint "LC-LQFP-144_20x20x05P")
      (libsource (lib "直流原理图库") (part "LPC1778LQFP144"))
    )
    (comp (ref "U4")
      (value "RSM485S_CTM8251T")
      (footprint "RSM485")
      (libsource (lib "*") (part "RSM485S_CTM8251T"))
    )
    (comp (ref "U5") (value "SP706SEN") (footprint "SOP8") (libsource (lib "*") (part "SP706SEN")))
    (comp (ref "U6")
      (value "RSM485S_CTM8251T")
      (footprint "RSM485")
      (libsource (lib "*") (part "RSM485S_CTM8251T"))
    )
    (comp (ref "U7") (value "SP3232") (footprint "SO-16") (libsource (lib "*") (part "MAX232ESE")))
    (comp (ref "U8") (value "CTM8251") (footprint "CTM8251KT") (libsource (lib "直流原理图库") (part "CTM8251")))
    (comp (ref "U9") (value "CTM8251") (footprint "CTM8251KT") (libsource (lib "直流原理图库") (part "CTM8251")))
    (comp (ref "U10") (value "FM25CL64") (footprint "SOP8") (libsource (lib "*") (part "FM25CL64")))
    (comp (ref "U11")
      (value "CJ431")
      (footprint "SOT23")
      (description "TL431,SOT23/ST/ON")
      (libsource (lib "*") (part "TL431"))
    )
    (comp (ref "U12")
      (value "HCNR201")
      (footprint "HCNR201-SMD")
      (libsource (lib "ueee20160531") (part "HCNR200"))
    )
    (comp (ref "U13")
      (value "ZY1212FKS-2W")
      (footprint "ZY1212FKS-2W")
      (libsource (lib "Aidane") (part "ZY1212FKS-2W"))
    )
    (comp (ref "U14") (value "LM358") (footprint "SOP8") (libsource (lib "*") (part "AS358P-E1")))
    (comp (ref "U15") (value "LM358") (footprint "SOP8") (libsource (lib "*") (part "AS358P-E1")))
    (comp (ref "U16") (value "LM78L05") (footprint "SOT-89") (libsource (lib "*") (part "LM7805")))
    (comp (ref "U17") (value "PRTR5V0U2X") (footprint "SOT-143B") (libsource (lib "*") (part "PRTR5V0U2X_1")))
    (comp (ref "UG1") (value "PS2501L-1") (footprint "DIP-4") (libsource (lib "") (part "PS2501-1_1")))
    (comp (ref "UG2") (value "PS2501L-1") (footprint "DIP-4") (libsource (lib "") (part "PS2501-1_1")))
    (comp (ref "UG3") (value "PS2501L-1") (footprint "DIP-4") (libsource (lib "") (part "PS2501-1_1")))
    (comp (ref "UG4") (value "PS2501L-1") (footprint "DIP-4") (libsource (lib "") (part "PS2501-1_1")))
    (comp (ref "UG5") (value "PS2501L-1") (footprint "DIP-4") (libsource (lib "") (part "PS2501-1_1")))
    (comp (ref "UG6") (value "PS2501L-1") (footprint "DIP-4") (libsource (lib "*") (part "PS2501-1")))
    (comp (ref "Y1") (value "32.768KHz") (footprint "ZS-32.768") (libsource (lib "*") (part "CRYSTAL")))
    (comp (ref "Y2") (value "12M") (footprint "ZS_SMD") (libsource (lib "*") (part "CRYSTAL")))
    (comp (ref "Z1") (value "1N4741") (footprint "1206D") (libsource (lib "*") (part "DIODE")))
  )
  (nets
    (net (code "1") (name "/485_CON1") (class "Default")
      (node (ref "U3") (pin "134") (pinfunction "P4[31]/EMC_CS1_134") (pintype "bidirectional"))
      (node (ref "U4") (pin "5") (pinfunction "485_CON_5") (pintype "passive"))
    )
    (net (code "2") (name "/485_CON2") (class "Default")
      (node (ref "U3") (pin "130") (pinfunction "P4[30]/EMC_CS0_130") (pintype "bidirectional"))
      (node (ref "U6") (pin "5") (pinfunction "485_CON_5") (pintype "passive"))
    )
    (net (code "3") (name "/ADC1-switch") (class "Default")
      (node (ref "U3") (pin "42") (pinfunction "P0[29]/USB_D+1/EINT0_42") (pintype "bidirectional"))
    )
    (net (code "4") (name "/ADC2-switch") (class "Default")
      (node (ref "U3") (pin "43") (pinfunction "P0[30]/USB_D-1/EINT1_43") (pintype "bidirectional"))
    )
    (net (code "5") (name "/ADC_CC1") (class "Default")
      (node (ref "C72") (pin "2") (pinfunction "2_2") (pintype "passive"))
      (node (ref "C73") (pin "2") (pinfunction "2_2") (pintype "passive"))
      (node (ref "C74") (pin "2") (pinfunction "2_2") (pintype "passive"))
      (node (ref "R86") (pin "2") (pinfunction "2_2") (pintype "passive"))
      (node (ref "R88") (pin "1") (pinfunction "1_1") (pintype "passive"))
      (node (ref "U3") (pin "30") (pinfunction "P1[30]/USB_PWRD2/USB_VBUS/ADC0_IN4/I2C0_SDA/U3_OE_30") (pintype "bidirectional"))
    )
    (net (code "6") (name "/ADC_CC2") (class "Default")
      (node (ref "U3") (pin "28") (pinfunction "P1[31]/USB_OVRCR2/SSP1_SCK/ADC0_IN5/I2C0_SCL_28") (pintype "bidirectional"))
    )
    (net (code "7") (name "/AGND") (class "Default")
      (node (ref "C42") (pin "2") (pintype "passive"))
      (node (ref "C43") (pin "2") (pintype "passive"))
      (node (ref "C44") (pin "2") (pinfunction "2_2") (pintype "passive"))
      (node (ref "L4") (pin "1") (pinfunction "1_1") (pintype "passive"))
      (node (ref "R58") (pin "1") (pinfunction "1_1") (pintype "passive"))
      (node (ref "U11") (pin "2") (pinfunction "A_2") (pintype "passive"))
      (node (ref "U3") (pin "15") (pinfunction "VSSA_15") (pintype "bidirectional"))
    )
    (net (code "8") (name "/CANH1") (class "Default")
      (node (ref "J7") (pin "6") (pinfunction "6_6") (pintype "passive"))
      (node (ref "J7") (pin "8") (pinfunction "8_8") (pintype "passive"))
      (node (ref "R39") (pin "2") (pinfunction "2_2") (pintype "passive"))
      (node (ref "TVS7") (pin "1") (pintype "passive"))
      (node (ref "U8") (pin "6") (pinfunction "CANH_6") (pintype "passive"))
    )
    (net (code "9") (name "/CANH2") (class "Default")
      (node (ref "J7") (pin "2") (pinfunction "2_2") (pintype "passive"))
      (node (ref "J7") (pin "4") (pinfunction "4_4") (pintype "passive"))
      (node (ref "R53") (pin "2") (pinfunction "2_2") (pintype "passive"))
      (node (ref "TVS11") (pin "1") (pintype "passive"))
      (node (ref "U9") (pin "6") (pinfunction "CANH_6") (pintype "passive"))
    )
    (net (code "10") (name "/CANL1") (class "Default")
      (node (ref "J7") (pin "5") (pinfunction "5_5") (pintype "passive"))
      (node (ref "J7") (pin "7") (pinfunction "7_7") (pintype "passive"))
      (node (ref "R39") (pin "1") (pinfunction "1_1") (pintype "passive"))
      (node (ref "TVS5") (pin "2") (pintype "passive"))
      (node (ref "TVS7") (pin "2") (pintype "passive"))
      (node (ref "U8") (pin "7") (pinfunction "CANL_7") (pintype "passive"))
    )
    (net (code "11") (name "/CANL2") (class "Default")
      (node (ref "J7") (pin "1") (pinfunction "1_1") (pintype "passive"))
      (node (ref "J7") (pin "3") (pinfunction "3_3") (pintype "passive"))
      (node (ref "R53") (pin "1") (pinfunction "1_1") (pintype "passive"))
      (node (ref "TVS10") (pin "2") (pintype "passive"))
      (node (ref "TVS11") (pin "2") (pintype "passive"))
      (node (ref "U9") (pin "7") (pinfunction "CANL_7") (pintype "passive"))
    )
    (net (code "12") (name "/CAN_RD1") (class "Default")
      (node (ref "R56") (pin "2") (pinfunction "2_2") (pintype "passive"))
      (node (ref "U3") (pin "82") (pinfunction "P0[21]/U1_RI/SD_PWR/U4_OE/CAN_RD1/U4_SCLK_82") (pintype "bidirectional"))
      (node (ref "U9") (pin "4") (pinfunction "RD_4") (pintype "passive"))
    )
    (net (code "13") (name "/CAN_RD2") (class "Default")
      (node (ref "R41") (pin "2") (pinfunction "2_2") (pintype "passive"))
      (node (ref "U3") (pin "95") (pinfunction "P2[7]/CAN_RD2/U1_RTS_95") (pintype "bidirectional"))
      (node (ref "U8") (pin "4") (pinfunction "RD_4") (pintype "passive"))
    )
    (net (code "14") (name "/CAN_TD1") (class "Default")
      (node (ref "R51") (pin "2") (pinfunction "2_2") (pintype "passive"))
      (node (ref "U3") (pin "80") (pinfunction "P0[22]/U1_RTS/SD_DAT0/U4_TXD/CAN_TD1_80") (pintype "bidirectional"))
      (node (ref "U9") (pin "3") (pinfunction "TD_3") (pintype "passive"))
    )
    (net (code "15") (name "/CAN_TD2") (class "Default")
      (node (ref "R38") (pin "2") (pinfunction "2_2") (pintype "passive"))
      (node (ref "U3") (pin "93") (pinfunction "P2[8]/CAN_TD2/U2_TXD/U1_CTS/ENET_MDC_93") (pintype "bidirectional"))
      (node (ref "U8") (pin "3") (pinfunction "TD_3") (pintype "passive"))
    )
    (net (code "16") (name "/CC1") (class "Default")
      (node (ref "J4") (pin "4") (pinfunction "4_4") (pintype "passive"))
      (node (ref "L5") (pin "1") (pinfunction "1_1") (pintype "passive"))
    )
    (net (code "17") (name "/DO1") (class "Default")
      (node (ref "R77") (pin "1") (pinfunction "1_1") (pintype "passive"))
      (node (ref "U3") (pin "38") (pinfunction "P3[26]/EMC_D[26]/PWM1[3]/T0_MAT1/STCLK_38") (pintype "bidirectional"))
    )
    (net (code "18") (name "/DO1-1") (class "Default")
      (node (ref "J8") (pin "1") (pinfunction "1_1") (pintype "passive"))
      (node (ref "RL1") (pin "3") (pinfunction "CM_3") (pintype "passive"))
    )
    (net (code "19") (name "/DO1-2") (class "Default")
      (node (ref "J8") (pin "2") (pinfunction "2_2") (pintype "passive"))
      (node (ref "RL1") (pin "4") (pinfunction "RO_4") (pintype "passive"))
    )
    (net (code "20") (name "/DO2") (class "Default")
      (node (ref "R80") (pin "1") (pinfunction "1_1") (pintype "passive"))
      (node (ref "U3") (pin "39") (pinfunction "P3[25]/EMC_D[25]/PWM1[2]/T0_MAT0_39") (pintype "bidirectional"))
    )
    (net (code "21") (name "/DO2-1") (class "Default")
      (node (ref "J8") (pin "3") (pinfunction "3_3") (pintype "passive"))
      (node (ref "RL2") (pin "3") (pinfunction "CM_3") (pintype "passive"))
    )
    (net (code "22") (name "/DO2-2") (class "Default")
      (node (ref "J8") (pin "4") (pinfunction "4_4") (pintype "passive"))
      (node (ref "RL2") (pin "4") (pinfunction "RO_4") (pintype "passive"))
    )
    (net (code "23") (name "/DO3") (class "Default")
      (node (ref "R102") (pin "1") (pinfunction "1_1") (pintype "passive"))
      (node (ref "U3") (pin "40") (pinfunction "P3[24]/EMC_D[24]/PWM1[1]/T0_CAP1_40") (pintype "bidirectional"))
    )
    (net (code "24") (name "/DO3-1") (class "Default")
      (node (ref "J8") (pin "5") (pinfunction "5_5") (pintype "passive"))
      (node (ref "RL3") (pin "3") (pinfunction "CM_3") (pintype "passive"))
    )
    (net (code "25") (name "/DO3-2") (class "Default")
      (node (ref "J8") (pin "6") (pinfunction "6_6") (pintype "passive"))
      (node (ref "RL3") (pin "4") (pinfunction "RO_4") (pintype "passive"))
    )
    (net (code "26") (name "/DO4") (class "Default")
      (node (ref "R98") (pin "1") (pinfunction "1_1") (pintype "passive"))
      (node (ref "U3") (pin "46") (pinfunction "P1[18]/USB_UP_LED1/PWM1[1]/T1CAP0/SSP1_MISO_46") (pintype "bidirectional"))
    )
    (net (code "27") (name "/DO4-1") (class "Default")
      (node (ref "J8") (pin "7") (pinfunction "7_7") (pintype "passive"))
      (node (ref "RL4") (pin "3") (pinfunction "CM_3") (pintype "passive"))
    )
    (net (code "28") (name "/DO4-2") (class "Default")
      (node (ref "J8") (pin "8") (pinfunction "8_8") (pintype "passive"))
      (node (ref "RL4") (pin "4") (pinfunction "RO_4") (pintype "passive"))
    )
    (net (code "29") (name "/DO5") (class "Default")
      (node (ref "R123") (pin "1") (pinfunction "1_1") (pintype "passive"))
      (node (ref "U3") (pin "47") (pinfunction "P1[19]/USB_TX_E1/USB_PPWR1/T1_CAP1/MC_0A/SSP1_SCK/U2_OE_47") (pintype "bidirectional"))
    )
    (net (code "30") (name "/DO5-1") (class "Default")
      (node (ref "J8") (pin "11") (pinfunction "11_11") (pintype "passive"))
      (node (ref "J8") (pin "9") (pinfunction "9_9") (pintype "passive"))
      (node (ref "RL5") (pin "3") (pinfunction "CM_3") (pintype "passive"))
    )
    (net (code "31") (name "/DO5-2") (class "Default")
      (node (ref "J8") (pin "10") (pinfunction "10_10") (pintype "passive"))
      (node (ref "J8") (pin "12") (pinfunction "12_12") (pintype "passive"))
      (node (ref "RL5") (pin "4") (pinfunction "RO_4") (pintype "passive"))
    )
    (net (code "32") (name "/EL1+") (class "Default")
      (node (ref "DC7") (pin "2") (pinfunction "2_2") (pintype "passive"))
      (node (ref "DC8") (pin "2") (pinfunction "2_2") (pintype "passive"))
      (node (ref "J9") (pin "11") (pinfunction "11_11") (pintype "passive"))
    )
    (net (code "33") (name "/FG") (class "Default")
      (node (ref "J4") (pin "3") (pinfunction "3_3") (pintype "passive"))
      (node (ref "L7") (pin "1") (pinfunction "1_1") (pintype "passive"))
    )
    (net (code "34") (name "/FRAM_CS") (class "Default")
      (node (ref "R52") (pin "2") (pinfunction "2_2") (pintype "passive"))
      (node (ref "U10") (pin "1") (pinfunction "~{CS}_1") (pintype "passive"))
      (node (ref "U3") (pin "90") (pinfunction "P0[16]/U1_RXD/SSP0_SSEL_90") (pintype "bidirectional"))
    )
    (net (code "35") (name "/FRAM_MISO") (class "Default")
      (node (ref "R50") (pin "2") (pinfunction "2_2") (pintype "passive"))
      (node (ref "U10") (pin "2") (pinfunction "SO_2") (pintype "passive"))
      (node (ref "U3") (pin "87") (pinfunction "P0[17]/U1_CTS/SSP0_MISO_87") (pintype "bidirectional"))
    )
    (net (code "36") (name "/FRAM_MOSI") (class "Default")
      (node (ref "R49") (pin "2") (pinfunction "2_2") (pintype "passive"))
      (node (ref "U10") (pin "5") (pinfunction "SI_5") (pintype "passive"))
      (node (ref "U3") (pin "86") (pinfunction "P0[18]/U1_DCD/SSP0_MOSI_86") (pintype "bidirectional"))
    )
    (net (code "37") (name "/FRAM_SCK") (class "Default")
      (node (ref "R48") (pin "2") (pinfunction "2_2") (pintype "passive"))
      (node (ref "U10") (pin "6") (pinfunction "SCK_6") (pintype "passive"))
      (node (ref "U3") (pin "89") (pinfunction "P0[15]/U1_TXD/SSP0_SCK_89") (pintype "bidirectional"))
    )
    (net (code "38") (name "/ISP") (class "Default")
      (node (ref "R15") (pin "1") (pintype "passive"))
      (node (ref "SW2") (pin "2") (pinfunction "NO_2") (pintype "passive"))
      (node (ref "U3") (pin "76") (pinfunction "P2[10]/EINT0/NMI_76") (pintype "bidirectional"))
    )
    (net (code "39") (name "/LOCK1") (class "Default")
      (node (ref "R133") (pin "1") (pinfunction "1_1") (pintype "passive"))
      (node (ref "U3") (pin "75") (pinfunction "P2[11]/EINT1/SD_DAT[1]/I2S_TX_SCK_75") (pintype "bidirectional"))
    )
    (net (code "40") (name "/LOCK2") (class "Default")
      (node (ref "U3") (pin "73") (pinfunction "P2[12]/EINT2/SD_DAT[2]/I2S_TX_WS_73") (pintype "bidirectional"))
    )
    (net (code "41") (name "/MODE1") (class "Default")
      (node (ref "R59") (pin "1") (pinfunction "1_1") (pintype "passive"))
      (node (ref "SW4") (pin "2") (pinfunction "NO_2") (pintype "passive"))
      (node (ref "U3") (pin "72") (pinfunction "P4[4]/EMC_A[4]_72") (pintype "bidirectional"))
    )
    (net (code "42") (name "/NCT-IN1") (class "Default")
      (node (ref "C62") (pin "1") (pintype "passive"))
      (node (ref "R66") (pin "2") (pinfunction "2_2") (pintype "passive"))
      (node (ref "U3") (pin "54") (pinfunction "P1[24]/USB_RX_DM1/PWM1[5]/QEI_IDX/MC_FB2/SSP0_MOSI_54") (pintype "bidirectional"))
      (node (ref "UG1") (pin "4") (pintype "passive"))
    )
    (net (code "43") (name "/NCT-IN2") (class "Default")
      (node (ref "C64") (pin "1") (pintype "passive"))
      (node (ref "R67") (pin "2") (pinfunction "2_2") (pintype "passive"))
      (node (ref "U3") (pin "56") (pinfunction "P1[25]/USB_LS1/USB_HSTEN1/T1_MAT1/MC_1A/CLKOUT_56") (pintype "bidirectional"))
      (node (ref "UG2") (pin "4") (pintype "passive"))
    )
    (net (code "44") (name "/NCT-IN3") (class "Default")
      (node (ref "C81") (pin "1") (pintype "passive"))
      (node (ref "R91") (pin "2") (pinfunction "2_2") (pintype "passive"))
      (node (ref "U3") (pin "57") (pinfunction "P1[26]/USB_SSPND1/PWM1[6]/T0_CAP0/MC_1B/SSP1_SSEL_57") (pintype "bidirectional"))
      (node (ref "UG3") (pin "4") (pintype "passive"))
    )
    (net (code "45") (name "/NCT-IN4") (class "Default")
      (node (ref "C83") (pin "1") (pintype "passive"))
      (node (ref "R92") (pin "2") (pinfunction "2_2") (pintype "passive"))
      (node (ref "U3") (pin "61") (pinfunction "P1[27]/USB_INT1/USB_OVRCR1/T0_CAP1/CLKOUT_61") (pintype "bidirectional"))
      (node (ref "UG4") (pin "4") (pintype "passive"))
    )
    (net (code "46") (name "/NCT-IN5") (class "Default")
      (node (ref "C98") (pin "1") (pintype "passive"))
      (node (ref "R113") (pin "2") (pinfunction "2_2") (pintype "passive"))
      (node (ref "U3") (pin "63") (pinfunction "P1[28]/USB_SCL1/PWM1_CAP0/T0_MAT0/MC_2A/SSP0_SSEL_63") (pintype "bidirectional"))
      (node (ref "UG5") (pin "4") (pintype "passive"))
    )
    (net (code "47") (name "/NCT-IN6") (class "Default")
      (node (ref "U3") (pin "64") (pinfunction "P1[29]/USB_SDA1/PWM1_CAP1]/T0_MAT1/MC_2B/U4_TXD_64") (pintype "bidirectional"))
    )
    (net (code "48") (name "/RTCK1") (class "Default")
      (node (ref "C45") (pin "1") (pinfunction "1_1") (pintype "passive"))
      (node (ref "U3") (pin "23") (pinfunction "RTCX1_23") (pintype "bidirectional"))
      (node (ref "Y1") (pin "1") (pinfunction "1_1") (pintype "passive"))
    )
    (net (code "49") (name "/RTCK2") (class "Default")
      (node (ref "C47") (pin "1") (pinfunction "1_1") (pintype "passive"))
      (node (ref "U3") (pin "25") (pinfunction "RTCX2_25") (pintype "bidirectional"))
      (node (ref "Y1") (pin "2") (pinfunction "2_2") (pintype "passive"))
    )
    (net (code "50") (name "/Run") (class "Default")
      (node (ref "R29") (pin "1") (pinfunction "1_1") (pintype "passive"))
      (node (ref "U3") (pin "96") (pinfunction "P2[6]/PWM1_CAP0/U1_RI/T2_CAP0/U2_OE/TRACECELK_96") (pintype "bidirectional"))
    )
    (net (code "51") (name "/STOP_TEST") (class "Default")
      (node (ref "U3") (pin "53") (pinfunction "P1[23]/USB_RX_DP1/PWM1[4]/QEI_PHB/MC_FB1/SSP0_MISO_53") (pintype "bidirectional"))
    )
    (net (code "52") (name "/TCK") (class "Default")
      (node (ref "J2") (pin "1") (pinfunction "1_1") (pintype "passive"))
      (node (ref "R30") (pin "1") (pinfunction "1_1") (pintype "passive"))
      (node (ref "U3") (pin "7") (pinfunction "JTAG_TCK_7") (pintype "bidirectional"))
    )
    (net (code "53") (name "/TDO") (class "Default")
      (node (ref "U3") (pin "1") (pinfunction "JTAG_TDO_1") (pintype "bidirectional"))
    )
    (net (code "54") (name "/TMS") (class "Default")
      (node (ref "J2") (pin "2") (pinfunction "2_2") (pintype "passive"))
      (node (ref "R31") (pin "1") (pinfunction "1_1") (pintype "passive"))
      (node (ref "U3") (pin "4") (pinfunction "JTAG_TMS_4") (pintype "bidirectional"))
    )
    (net (code "55") (name "/U0-RX") (class "Default")
      (node (ref "J6") (pin "11") (pinfunction "11_11") (pintype "passive"))
      (node (ref "R138") (pin "2") (pintype "passive"))
    )
    (net (code "56") (name "/U0-RXD") (class "Default")
      (node (ref "R40") (pin "1") (pintype "passive"))
      (node (ref "U3") (pin "142") (pinfunction "P0[3]/U0_RXD/U3_RXD_142") (pintype "bidirectional"))
    )
    (net (code "57") (name "/U0-TX") (class "Default")
      (node (ref "J6") (pin "10") (pinfunction "10_10") (pintype "passive"))
      (node (ref "R139") (pin "2") (pintype "passive"))
    )
    (net (code "58") (name "/U0-TXD") (class "Default")
      (node (ref "R43") (pin "1") (pintype "passive"))
      (node (ref "U3") (pin "141") (pinfunction "P0[2]/U0_TXD/U3_TXD_141") (pintype "bidirectional"))
    )
    (net (code "59") (name "/U1-RX") (class "Default")
      (node (ref "J6") (pin "7") (pinfunction "7_7") (pintype "passive"))
      (node (ref "R37") (pin "2") (pintype "passive"))
      (node (ref "TVS6") (pin "2") (pintype "passive"))
      (node (ref "TVS8") (pin "2") (pintype "passive"))
    )
    (net (code "60") (name "/U1-TX") (class "Default")
      (node (ref "J6") (pin "6") (pinfunction "6_6") (pintype "passive"))
      (node (ref "R45") (pin "2") (pintype "passive"))
      (node (ref "TVS8") (pin "1") (pintype "passive"))
    )
    (net (code "61") (name "/U1_RXD") (class "Default")
      (node (ref "D5") (pin "2") (pintype "passive"))
      (node (ref "R34") (pin "1") (pintype "passive"))
      (node (ref "U3") (pin "106") (pinfunction "P2[1]/PWM1[2]/U1_RXD_106") (pintype "bidirectional"))
    )
    (net (code "62") (name "/U1_TXD") (class "Default")
      (node (ref "D6") (pin "2") (pintype "passive"))
      (node (ref "R32") (pin "1") (pintype "passive"))
      (node (ref "U3") (pin "107") (pinfunction "P2[0]/PWM1[1]/U1_TXD_107") (pintype "bidirectional"))
    )
    (net (code "63") (name "/U2_RXD") (class "Default")
      (node (ref "U3") (pin "70") (pinfunction "P0[11]/U2_RXD/I2C2_SCL/T3_MAT1_70") (pintype "bidirectional"))
    )
    (net (code "64") (name "/U2_TXD") (class "Default")
      (node (ref "U3") (pin "69") (pinfunction "P0[10]/U2_TXD/I2C2_SDA/T3_MAT0_69") (pintype "bidirectional"))
    )
    (net (code "65") (name "/U3_485A") (class "Default")
      (node (ref "J6") (pin "2") (pinfunction "2_2") (pintype "passive"))
      (node (ref "J6") (pin "4") (pinfunction "4_4") (pintype "passive"))
      (node (ref "R11") (pin "2") (pintype "passive"))
      (node (ref "TVS2") (pin "2") (pintype "passive"))
    )
    (net (code "66") (name "/U3_485B") (class "Default")
      (node (ref "J6") (pin "1") (pinfunction "1_1") (pintype "passive"))
      (node (ref "J6") (pin "3") (pinfunction "3_3") (pintype "passive"))
      (node (ref "R14") (pin "2") (pintype "passive"))
      (node (ref "TVS1") (pin "2") (pintype "passive"))
      (node (ref "TVS2") (pin "1") (pintype "passive"))
    )
    (net (code "67") (name "/U3_RXD") (class "Default")
      (node (ref "R42") (pin "1") (pintype "passive"))
      (node (ref "U3") (pin "122") (pinfunction "P4[29]/EMC_BLS3/U3_RXD/T2_MAT1/I2C2_SCL_122") (pintype "bidirectional"))
    )
    (net (code "68") (name "/U3_TXD") (class "Default")
      (node (ref "R44") (pin "1") (pintype "passive"))
      (node (ref "U3") (pin "118") (pinfunction "P4[28]/EMC_ABLS2/U3_TXD/T2_MAT0_118") (pintype "bidirectional"))
    )
    (net (code "69") (name "/U4_485A") (class "Default")
      (node (ref "J7") (pin "10") (pinfunction "10_10") (pintype "passive"))
      (node (ref "J7") (pin "12") (pinfunction "12_12") (pintype "passive"))
      (node (ref "R28") (pin "2") (pintype "passive"))
      (node (ref "TVS4") (pin "2") (pintype "passive"))
    )
    (net (code "70") (name "/U4_485B") (class "Default")
      (node (ref "J7") (pin "11") (pinfunction "11_11") (pintype "passive"))
      (node (ref "J7") (pin "9") (pinfunction "9_9") (pintype "passive"))
      (node (ref "R35") (pin "2") (pintype "passive"))
      (node (ref "TVS3") (pin "2") (pintype "passive"))
      (node (ref "TVS4") (pin "1") (pintype "passive"))
    )
    (net (code "71") (name "/U4_RXD") (class "Default")
      (node (ref "D3") (pin "2") (pintype "passive"))
      (node (ref "R13") (pin "1") (pintype "passive"))
      (node (ref "U3") (pin "98") (pinfunction "P5[3]/U4_RXD//I2C0_SCL_98") (pintype "bidirectional"))
    )
    (net (code "72") (name "/U4_TXD") (class "Default")
      (node (ref "D4") (pin "2") (pintype "passive"))
      (node (ref "R12") (pin "1") (pintype "passive"))
      (node (ref "U3") (pin "143") (pinfunction "P5[4]/U0_OE/T3_MAT3/U4_TXD_143") (pintype "bidirectional"))
    )
    (net (code "73") (name "/USBD2+") (class "Default")
      (node (ref "R217") (pin "2") (pinfunction "2_2") (pintype "passive"))
      (node (ref "U3") (pin "36") (pinfunction "P0[31]/USB_D+2_36") (pintype "bidirectional"))
    )
    (net (code "74") (name "/USBD2-") (class "Default")
      (node (ref "R216") (pin "2") (pinfunction "2_2") (pintype "passive"))
      (node (ref "U3") (pin "37") (pinfunction "USB_D-2_37") (pintype "bidirectional"))
    )
    (net (code "76") (name "/WDI") (class "Default")
      (node (ref "R19") (pin "2") (pinfunction "2_2") (pintype "passive"))
      (node (ref "U3") (pin "35") (pinfunction "P0[27]/I2C0_SDA/USB_SDA1_35") (pintype "bidirectional"))
      (node (ref "U5") (pin "6") (pinfunction "WDI_6") (pintype "passive"))
    )
    (net (code "77") (name "/XTAL1") (class "Default")
      (node (ref "C46") (pin "1") (pinfunction "1_1") (pintype "passive"))
      (node (ref "U3") (pin "31") (pinfunction "XTAL1_31") (pintype "bidirectional"))
      (node (ref "Y2") (pin "2") (pinfunction "2_2") (pintype "passive"))
    )
    (net (code "78") (name "/XTAL2") (class "Default")
      (node (ref "C48") (pin "1") (pinfunction "1_1") (pintype "passive"))
      (node (ref "U3") (pin "33") (pinfunction "XTAL2_33") (pintype "bidirectional"))
      (node (ref "Y2") (pin "1") (pinfunction "1_1") (pintype "passive"))
    )
    (net (code "79") (name "/Y1-in") (class "Default")
      (node (ref "J9") (pin "1") (pinfunction "1_1") (pintype "passive"))
      (node (ref "R71") (pin "1") (pinfunction "1_1") (pintype "passive"))
    )
    (net (code "80") (name "/Y2-in") (class "Default")
      (node (ref "J9") (pin "3") (pinfunction "3_3") (pintype "passive"))
      (node (ref "R72") (pin "1") (pinfunction "1_1") (pintype "passive"))
    )
    (net (code "81") (name "/Y3-in") (class "Default")
      (node (ref "J9") (pin "5") (pinfunction "5_5") (pintype "passive"))
      (node (ref "R89") (pin "1") (pinfunction "1_1") (pintype "passive"))
    )
    (net (code "82") (name "/Y4-in") (class "Default")
      (node (ref "J9") (pin "7") (pinfunction "7_7") (pintype "passive"))
      (node (ref "R90") (pin "1") (pinfunction "1_1") (pintype "passive"))
    )
    (net (code "83") (name "/Y5-in") (class "Default")
      (node (ref "J9") (pin "9") (pinfunction "9_9") (pintype "passive"))
      (node (ref "R117") (pin "1") (pintype "passive"))
    )
    (net (code "84") (name "/in-ad1") (class "Default")
      (node (ref "R70") (pin "2") (pinfunction "2_2") (pintype "passive"))
      (node (ref "U12") (pin "3") (pintype "passive"))
      (node (ref "U14") (pin "2") (pinfunction "IN-_2") (pintype "passive"))
    )
    (net (code "85") (name "/nRST") (class "Default")
      (node (ref "C28") (pin "2") (pinfunction "2_2") (pintype "passive"))
      (node (ref "R21") (pin "2") (pinfunction "2_2") (pintype "passive"))
      (node (ref "R27") (pin "2") (pinfunction "2_2") (pintype "passive"))
      (node (ref "U3") (pin "24") (pinfunction "RESET_24") (pintype "bidirectional"))
    )
    (net (code "86") (name "/sw0") (class "Default")
      (node (ref "C17") (pin "1") (pintype "passive"))
      (node (ref "L1") (pin "1") (pinfunction "1_1") (pintype "passive"))
      (node (ref "U1") (pin "3") (pinfunction "SW_3") (pintype "passive"))
    )
    (net (code "87") (name "12VS") (class "Default")
      (node (ref "C61") (pin "1") (pintype "passive"))
      (node (ref "C63") (pin "1") (pintype "passive"))
      (node (ref "C77") (pin "1") (pinfunction "1_1") (pintype "passive"))
      (node (ref "C80") (pin "1") (pintype "passive"))
      (node (ref "C82") (pin "1") (pintype "passive"))
      (node (ref "C97") (pin "2") (pintype "passive"))
      (node (ref "D1") (pin "1") (pinfunction "A_1") (pintype "passive"))
      (node (ref "D2") (pin "1") (pinfunction "A_1") (pintype "passive"))
      (node (ref "J4") (pin "1") (pinfunction "1_1") (pintype "passive"))
      (node (ref "Q17") (pin "3") (pinfunction "S_3") (pintype "passive"))
      (node (ref "R127") (pin "2") (pinfunction "2_2") (pintype "passive"))
      (node (ref "U13") (pin "1") (pinfunction "Vin_1") (pintype "passive"))
      (node (ref "UG1") (pin "1") (pintype "passive"))
      (node (ref "UG2") (pin "1") (pintype "passive"))
      (node (ref "UG3") (pin "1") (pintype "passive"))
      (node (ref "UG4") (pin "1") (pintype "passive"))
      (node (ref "UG5") (pin "1") (pintype "passive"))
    )
    (net (code "88") (name "DGND") (class "Default")
      (node (ref "C1") (pin "2") (pinfunction "2_2") (pintype "passive"))
      (node (ref "C10") (pin "2") (pinfunction "2_2") (pintype "passive"))
      (node (ref "C108") (pin "1") (pinfunction "1_1") (pintype "passive"))
      (node (ref "C11") (pin "2") (pinfunction "2_2") (pintype "passive"))
      (node (ref "C12") (pin "1") (pinfunction "1_1") (pintype "passive"))
      (node (ref "C13") (pin "2") (pinfunction "2_2") (pintype "passive"))
      (node (ref "C14") (pin "2") (pinfunction "2_2") (pintype "passive"))
      (node (ref "C15") (pin "2") (pinfunction "2_2") (pintype "passive"))
      (node (ref "C16") (pin "2") (pinfunction "2_2") (pintype "passive"))
      (node (ref "C18") (pin "1") (pintype "passive"))
      (node (ref "C19") (pin "1") (pintype "passive"))
      (node (ref "C2") (pin "2") (pinfunction "2_2") (pintype "passive"))
      (node (ref "C20") (pin "1") (pintype "passive"))
      (node (ref "C22") (pin "2") (pinfunction "2_2") (pintype "passive"))
      (node (ref "C23") (pin "2") (pintype "passive"))
      (node (ref "C25") (pin "2") (pinfunction "2_2") (pintype "passive"))
      (node (ref "C26") (pin "2") (pintype "passive"))
      (node (ref "C27") (pin "1") (pinfunction "1_1") (pintype "passive"))
      (node (ref "C28") (pin "1") (pinfunction "1_1") (pintype "passive"))
      (node (ref "C3") (pin "2") (pinfunction "2_2") (pintype "passive"))
      (node (ref "C33") (pin "1") (pintype "passive"))
      (node (ref "C34") (pin "2") (pinfunction "2_2") (pintype "passive"))
      (node (ref "C35") (pin "2") (pintype "passive"))
      (node (ref "C37") (pin "1") (pintype "passive"))
      (node (ref "C39") (pin "2") (pinfunction "2_2") (pintype "passive"))
      (node (ref "C4") (pin "2") (pinfunction "2_2") (pintype "passive"))
      (node (ref "C40") (pin "1") (pintype "passive"))
      (node (ref "C41") (pin "2") (pinfunction "2_2") (pintype "passive"))
      (node (ref "C45") (pin "2") (pinfunction "2_2") (pintype "passive"))
      (node (ref "C46") (pin "2") (pinfunction "2_2") (pintype "passive"))
      (node (ref "C47") (pin "2") (pinfunction "2_2") (pintype "passive"))
      (node (ref "C48") (pin "2") (pinfunction "2_2") (pintype "passive"))
      (node (ref "C5") (pin "2") (pinfunction "2_2") (pintype "passive"))
      (node (ref "C6") (pin "2") (pinfunction "2_2") (pintype "passive"))
      (node (ref "C62") (pin "2") (pintype "passive"))
      (node (ref "C64") (pin "2") (pintype "passive"))
      (node (ref "C65") (pin "2") (pintype "passive"))
      (node (ref "C66") (pin "1") (pinfunction "1_1") (pintype "passive"))
      (node (ref "C7") (pin "2") (pinfunction "2_2") (pintype "passive"))
      (node (ref "C72") (pin "1") (pinfunction "1_1") (pintype "passive"))
      (node (ref "C73") (pin "1") (pinfunction "1_1") (pintype "passive"))
      (node (ref "C74") (pin "1") (pinfunction "1_1") (pintype "passive"))
      (node (ref "C75") (pin "1") (pinfunction "1_1") (pintype "passive"))
      (node (ref "C76") (pin "1") (pinfunction "1_1") (pintype "passive"))
      (node (ref "C8") (pin "2") (pinfunction "2_2") (pintype "passive"))
      (node (ref "C81") (pin "2") (pintype "passive"))
      (node (ref "C83") (pin "2") (pintype "passive"))
      (node (ref "C88") (pin "2") (pintype "passive"))
      (node (ref "C9") (pin "2") (pinfunction "2_2") (pintype "passive"))
      (node (ref "C91") (pin "1") (pinfunction "1_1") (pintype "passive"))
      (node (ref "C98") (pin "2") (pintype "passive"))
      (node (ref "DC1") (pin "2") (pinfunction "2_2") (pintype "passive"))
      (node (ref "DC10") (pin "2") (pinfunction "2_2") (pintype "passive"))
      (node (ref "DC2") (pin "2") (pinfunction "2_2") (pintype "passive"))
      (node (ref "DC9") (pin "2") (pinfunction "2_2") (pintype "passive"))
      (node (ref "J12") (pin "4") (pinfunction "4_4") (pintype "passive"))
      (node (ref "J2") (pin "3") (pinfunction "3_3") (pintype "passive"))
      (node (ref "J6") (pin "5") (pinfunction "5_5") (pintype "passive"))
      (node (ref "J6") (pin "9") (pinfunction "9_9") (pintype "passive"))
      (node (ref "L2") (pin "2") (pinfunction "2_2") (pintype "passive"))
      (node (ref "L3") (pin "2") (pinfunction "2_2") (pintype "passive"))
      (node (ref "L4") (pin "2") (pinfunction "2_2") (pintype "passive"))
      (node (ref "Q1") (pin "3") (pinfunction "E_3") (pintype "input"))
      (node (ref "Q10") (pin "3") (pinfunction "E_3") (pintype "input"))
      (node (ref "Q11") (pin "3") (pinfunction "E_3") (pintype "input"))
      (node (ref "Q15") (pin "3") (pinfunction "E_3") (pintype "input"))
      (node (ref "Q3") (pin "3") (pinfunction "E_3") (pintype "input"))
      (node (ref "Q6") (pin "3") (pinfunction "E_3") (pintype "input"))
      (node (ref "Q7") (pin "3") (pinfunction "E_3") (pintype "input"))
      (node (ref "R107") (pin "1") (pinfunction "1_1") (pintype "passive"))
      (node (ref "R111") (pin "1") (pinfunction "1_1") (pintype "passive"))
      (node (ref "R125") (pin "1") (pinfunction "1_1") (pintype "passive"))
      (node (ref "R135") (pin "1") (pinfunction "1_1") (pintype "passive"))
      (node (ref "R218") (pin "1") (pinfunction "1_1") (pintype "passive"))
      (node (ref "R219") (pin "1") (pinfunction "1_1") (pintype "passive"))
      (node (ref "R33") (pin "1") (pinfunction "1_1") (pintype "passive"))
      (node (ref "R5") (pin "2") (pintype "passive"))
      (node (ref "R6") (pin "1") (pinfunction "1_1") (pintype "passive"))
      (node (ref "R7") (pin "2") (pintype "passive"))
      (node (ref "R83") (pin "1") (pinfunction "1_1") (pintype "passive"))
      (node (ref "R84") (pin "1") (pinfunction "1_1") (pintype "passive"))
      (node (ref "R88") (pin "2") (pinfunction "2_2") (pintype "passive"))
      (node (ref "SW2") (pin "1") (pinfunction "COMMON_1") (pintype "passive"))
      (node (ref "SW3") (pin "2") (pinfunction "2_2") (pintype "passive"))
      (node (ref "SW4") (pin "1") (pinfunction "COMMON_1") (pintype "passive"))
      (node (ref "TVS6") (pin "1") (pintype "passive"))
      (node (ref "U1") (pin "4") (pinfunction "GND_4") (pintype "passive"))
      (node (ref "U10") (pin "4") (pinfunction "VSS_4") (pintype "passive"))
      (node (ref "U12") (pin "5") (pintype "passive"))
      (node (ref "U15") (pin "3") (pinfunction "IN+_3") (pintype "passive"))
      (node (ref "U15") (pin "4") (pinfunction "GND_4") (pintype "passive"))
      (node (ref "U17") (pin "1") (pinfunction "GND_1") (pintype "passive"))
      (node (ref "U2") (pin "3") (pinfunction "Gnd_3") (pintype "passive"))
      (node (ref "U2") (pin "6") (pinfunction "G_6") (pintype "passive"))
      (node (ref "U3") (pin "103") (pinfunction "VSS_103") (pintype "bidirectional"))
      (node (ref "U3") (pin "117") (pinfunction "VSS_117") (pintype "bidirectional"))
      (node (ref "U3") (pin "119") (pinfunction "VSSREG_119") (pintype "bidirectional"))
      (node (ref "U3") (pin "139") (pinfunction "VSS_139") (pintype "bidirectional"))
      (node (ref "U3") (pin "22") (pinfunction "VSSREG_22") (pintype "bidirectional"))
      (node (ref "U3") (pin "44") (pinfunction "VSS_44") (pintype "bidirectional"))
      (node (ref "U3") (pin "59") (pinfunction "VSSREG_59") (pintype "bidirectional"))
      (node (ref "U3") (pin "65") (pinfunction "VSS_65") (pintype "bidirectional"))
      (node (ref "U3") (pin "79") (pinfunction "VSS_79") (pintype "bidirectional"))
      (node (ref "U4") (pin "2") (pinfunction "GND_2") (pintype "passive"))
      (node (ref "U5") (pin "3") (pinfunction "GND_3") (pintype "passive"))
      (node (ref "U5") (pin "4") (pinfunction "PFI_4") (pintype "passive"))
      (node (ref "U6") (pin "2") (pinfunction "GND_2") (pintype "passive"))
      (node (ref "U7") (pin "15") (pinfunction "GND_15") (pintype "passive"))
      (node (ref "U8") (pin "2") (pinfunction "GND_2") (pintype "passive"))
      (node (ref "U9") (pin "2") (pinfunction "GND_2") (pintype "passive"))
      (node (ref "UG1") (pin "3") (pintype "passive"))
      (node (ref "UG2") (pin "3") (pintype "passive"))
      (node (ref "UG3") (pin "3") (pintype "passive"))
      (node (ref "UG4") (pin "3") (pintype "passive"))
      (node (ref "UG5") (pin "3") (pintype "passive"))
    )
    (net (code "89") (name "DP3V3") (class "Default")
      (node (ref "C1") (pin "1") (pinfunction "1_1") (pintype "passive"))
      (node (ref "C10") (pin "1") (pinfunction "1_1") (pintype "passive"))
      (node (ref "C11") (pin "1") (pinfunction "1_1") (pintype "passive"))
      (node (ref "C12") (pin "2") (pinfunction "2_2") (pintype "passive"))
      (node (ref "C13") (pin "1") (pinfunction "1_1") (pintype "passive"))
      (node (ref "C14") (pin "1") (pinfunction "1_1") (pintype "passive"))
      (node (ref "C15") (pin "1") (pinfunction "1_1") (pintype "passive"))
      (node (ref "C16") (pin "1") (pinfunction "1_1") (pintype "passive"))
      (node (ref "C2") (pin "1") (pinfunction "1_1") (pintype "passive"))
      (node (ref "C22") (pin "1") (pinfunction "1_1") (pintype "passive"))
      (node (ref "C23") (pin "1") (pintype "passive"))
      (node (ref "C24") (pin "1") (pinfunction "1_1") (pintype "passive"))
      (node (ref "C25") (pin "1") (pinfunction "1_1") (pintype "passive"))
      (node (ref "C26") (pin "1") (pintype "passive"))
      (node (ref "C3") (pin "1") (pinfunction "1_1") (pintype "passive"))
      (node (ref "C32") (pin "2") (pintype "passive"))
      (node (ref "C33") (pin "2") (pintype "passive"))
      (node (ref "C34") (pin "1") (pinfunction "1_1") (pintype "passive"))
      (node (ref "C35") (pin "1") (pintype "passive"))
      (node (ref "C39") (pin "1") (pinfunction "1_1") (pintype "passive"))
      (node (ref "C4") (pin "1") (pinfunction "1_1") (pintype "passive"))
      (node (ref "C40") (pin "2") (pintype "passive"))
      (node (ref "C41") (pin "1") (pinfunction "1_1") (pintype "passive"))
      (node (ref "C5") (pin "1") (pinfunction "1_1") (pintype "passive"))
      (node (ref "C6") (pin "1") (pinfunction "1_1") (pintype "passive"))
      (node (ref "C7") (pin "1") (pinfunction "1_1") (pintype "passive"))
      (node (ref "C8") (pin "1") (pinfunction "1_1") (pintype "passive"))
      (node (ref "C9") (pin "1") (pinfunction "1_1") (pintype "passive"))
      (node (ref "D10") (pin "1") (pintype "passive"))
      (node (ref "D11") (pin "1") (pintype "passive"))
      (node (ref "D7") (pin "1") (pintype "passive"))
      (node (ref "D8") (pin "1") (pintype "passive"))
      (node (ref "D9") (pin "1") (pinfunction "A_1") (pintype "passive"))
      (node (ref "DC10") (pin "1") (pinfunction "1_1") (pintype "passive"))
      (node (ref "DC9") (pin "1") (pinfunction "1_1") (pintype "passive"))
      (node (ref "J2") (pin "4") (pinfunction "4_4") (pintype "passive"))
      (node (ref "R113") (pin "1") (pinfunction "1_1") (pintype "passive"))
      (node (ref "R129") (pin "1") (pinfunction "1_1") (pintype "passive"))
      (node (ref "R15") (pin "2") (pintype "passive"))
      (node (ref "R16") (pin "2") (pinfunction "2_2") (pintype "passive"))
      (node (ref "R18") (pin "2") (pinfunction "2_2") (pintype "passive"))
      (node (ref "R19") (pin "1") (pinfunction "1_1") (pintype "passive"))
      (node (ref "R20") (pin "1") (pinfunction "1_1") (pintype "passive"))
      (node (ref "R21") (pin "1") (pinfunction "1_1") (pintype "passive"))
      (node (ref "R22") (pin "2") (pintype "passive"))
      (node (ref "R23") (pin "2") (pintype "passive"))
      (node (ref "R3") (pin "2") (pinfunction "2_2") (pintype "passive"))
      (node (ref "R30") (pin "2") (pinfunction "2_2") (pintype "passive"))
      (node (ref "R31") (pin "2") (pinfunction "2_2") (pintype "passive"))
      (node (ref "R47") (pin "1") (pinfunction "1_1") (pintype "passive"))
      (node (ref "R48") (pin "1") (pinfunction "1_1") (pintype "passive"))
      (node (ref "R49") (pin "1") (pinfunction "1_1") (pintype "passive"))
      (node (ref "R50") (pin "1") (pinfunction "1_1") (pintype "passive"))
      (node (ref "R52") (pin "1") (pinfunction "1_1") (pintype "passive"))
      (node (ref "R54") (pin "1") (pinfunction "1_1") (pintype "passive"))
      (node (ref "R59") (pin "2") (pinfunction "2_2") (pintype "passive"))
      (node (ref "R66") (pin "1") (pinfunction "1_1") (pintype "passive"))
      (node (ref "R67") (pin "1") (pinfunction "1_1") (pintype "passive"))
      (node (ref "R8") (pin "2") (pintype "passive"))
      (node (ref "R9") (pin "2") (pintype "passive"))
      (node (ref "R91") (pin "1") (pinfunction "1_1") (pintype "passive"))
      (node (ref "R92") (pin "1") (pinfunction "1_1") (pintype "passive"))
      (node (ref "U10") (pin "8") (pinfunction "VDD_8") (pintype "passive"))
      (node (ref "U2") (pin "4") (pinfunction "Vout_4") (pintype "passive"))
      (node (ref "U3") (pin "102") (pinfunction "VDD_102") (pintype "bidirectional"))
      (node (ref "U3") (pin "114") (pinfunction "VDD_114") (pintype "bidirectional"))
      (node (ref "U3") (pin "121") (pinfunction "VDD_121") (pintype "bidirectional"))
      (node (ref "U3") (pin "138") (pinfunction "VDD_138") (pintype "bidirectional"))
      (node (ref "U3") (pin "18") (pinfunction "VDD_18") (pintype "bidirectional"))
      (node (ref "U3") (pin "41") (pinfunction "VDD_41") (pintype "bidirectional"))
      (node (ref "U3") (pin "60") (pinfunction "VDD_60") (pintype "bidirectional"))
      (node (ref "U3") (pin "62") (pinfunction "VDD_62") (pintype "bidirectional"))
      (node (ref "U3") (pin "77") (pinfunction "VDD_77") (pintype "bidirectional"))
      (node (ref "U4") (pin "1") (pinfunction "VCC_1") (pintype "passive"))
      (node (ref "U5") (pin "2") (pinfunction "VCC_2") (pintype "passive"))
      (node (ref "U6") (pin "1") (pinfunction "VCC_1") (pintype "passive"))
      (node (ref "U7") (pin "16") (pinfunction "VCC_16") (pintype "passive"))
      (node (ref "U8") (pin "1") (pinfunction "VCC_1") (pintype "passive"))
      (node (ref "U9") (pin "1") (pinfunction "VCC_1") (pintype "passive"))
    )
    (net (code "90") (name "FV5V") (class "Default")
      (node (ref "C69") (pin "2") (pinfunction "2_2") (pintype "passive"))
      (node (ref "C70") (pin "1") (pinfunction "1_1") (pintype "passive"))
      (node (ref "C78") (pin "2") (pintype "passive"))
      (node (ref "DC5") (pin "1") (pinfunction "1_1") (pintype "passive"))
      (node (ref "U12") (pin "2") (pintype "passive"))
      (node (ref "U14") (pin "8") (pinfunction "VCC_8") (pintype "passive"))
      (node (ref "U16") (pin "1") (pinfunction "OUT_1") (pintype "passive"))
    )
    (net (code "91") (name "FV11") (class "Default")
      (node (ref "C55") (pin "1") (pintype "passive"))
      (node (ref "C71") (pin "2") (pintype "passive"))
      (node (ref "DC3") (pin "2") (pinfunction "2_2") (pintype "passive"))
      (node (ref "DC4") (pin "1") (pinfunction "1_1") (pintype "passive"))
      (node (ref "R64") (pin "2") (pintype "passive"))
      (node (ref "R73") (pin "2") (pinfunction "2_2") (pintype "passive"))
      (node (ref "R74") (pin "2") (pinfunction "2_2") (pintype "passive"))
      (node (ref "Z1") (pin "2") (pinfunction "K_2") (pintype "passive"))
    )
    (net (code "92") (name "FV12") (class "Default")
      (node (ref "C55") (pin "2") (pintype "passive"))
      (node (ref "DC11") (pin "1") (pinfunction "1_1") (pintype "passive"))
      (node (ref "DC3") (pin "1") (pinfunction "1_1") (pintype "passive"))
      (node (ref "R73") (pin "1") (pinfunction "1_1") (pintype "passive"))
      (node (ref "R74") (pin "1") (pinfunction "1_1") (pintype "passive"))
      (node (ref "U13") (pin "7") (pinfunction "+Vo_7") (pintype "passive"))
      (node (ref "U16") (pin "3") (pinfunction "IN_3") (pintype "passive"))
    )
    (net (code "93") (name "FVGND") (class "Default")
      (node (ref "C58") (pin "1") (pinfunction "1_1") (pintype "passive"))
      (node (ref "C59") (pin "2") (pinfunction "2_2") (pintype "passive"))
      (node (ref "C60") (pin "2") (pinfunction "2_2") (pintype "passive"))
      (node (ref "C69") (pin "1") (pinfunction "1_1") (pintype "passive"))
      (node (ref "C70") (pin "2") (pinfunction "2_2") (pintype "passive"))
      (node (ref "C71") (pin "1") (pintype "passive"))
      (node (ref "C78") (pin "1") (pintype "passive"))
      (node (ref "DC11") (pin "2") (pinfunction "2_2") (pintype "passive"))
      (node (ref "DC4") (pin "2") (pinfunction "2_2") (pintype "passive"))
      (node (ref "DC5") (pin "2") (pinfunction "2_2") (pintype "passive"))
      (node (ref "L8") (pin "2") (pinfunction "2_2") (pintype "passive"))
      (node (ref "R81") (pin "1") (pinfunction "1_1") (pintype "passive"))
      (node (ref "U12") (pin "4") (pintype "passive"))
      (node (ref "U13") (pin "5") (pinfunction "0V_5") (pintype "passive"))
      (node (ref "U14") (pin "3") (pinfunction "IN+_3") (pintype "passive"))
      (node (ref "U14") (pin "4") (pinfunction "GND_4") (pintype "passive"))
      (node (ref "U16") (pin "2") (pinfunction "GND_2") (pintype "passive"))
      (node (ref "Z1") (pin "1") (pinfunction "A_1") (pintype "passive"))
    )
    (net (code "94") (name "Net-(C21-Pad2)") (class "Default")
      (node (ref "C21") (pin "2") (pintype "passive"))
      (node (ref "R7") (pin "1") (pintype "passive"))
    )
    (net (code "95") (name "Net-(C30-Pad1)") (class "Default")
      (node (ref "C30") (pin "1") (pinfunction "1_1") (pintype "passive"))
      (node (ref "R36") (pin "1") (pinfunction "1_1") (pintype "passive"))
      (node (ref "TVS5") (pin "1") (pintype "passive"))
    )
    (net (code "96") (name "Net-(C38-Pad2)") (class "Default")
      (node (ref "C38") (pin "2") (pinfunction "2_2") (pintype "passive"))
      (node (ref "R46") (pin "2") (pinfunction "2_2") (pintype "passive"))
      (node (ref "TVS10") (pin "1") (pintype "passive"))
    )
    (net (code "97") (name "Net-(C56-Pad1)") (class "Default")
      (node (ref "C56") (pin "1") (pinfunction "1_1") (pintype "passive"))
      (node (ref "L6") (pin "1") (pinfunction "1_1") (pintype "passive"))
      (node (ref "R75") (pin "2") (pinfunction "2_2") (pintype "passive"))
    )
    (net (code "98") (name "Net-(C56-Pad2)") (class "Default")
      (node (ref "C56") (pin "2") (pinfunction "2_2") (pintype "passive"))
      (node (ref "L8") (pin "1") (pinfunction "1_1") (pintype "passive"))
      (node (ref "R87") (pin "2") (pinfunction "2_2") (pintype "passive"))
    )
    (net (code "99") (name "Net-(C58-Pad2)") (class "Default")
      (node (ref "C58") (pin "2") (pinfunction "2_2") (pintype "passive"))
      (node (ref "C59") (pin "1") (pinfunction "1_1") (pintype "passive"))
      (node (ref "C60") (pin "1") (pinfunction "1_1") (pintype "passive"))
      (node (ref "L6") (pin "2") (pinfunction "2_2") (pintype "passive"))
      (node (ref "R68") (pin "1") (pinfunction "1_1") (pintype "passive"))
    )
    (net (code "100") (name "Net-(C61-Pad2)") (class "Default")
      (node (ref "C61") (pin "2") (pintype "passive"))
      (node (ref "R71") (pin "2") (pinfunction "2_2") (pintype "passive"))
      (node (ref "UG1") (pin "2") (pintype "passive"))
    )
    (net (code "101") (name "Net-(C63-Pad2)") (class "Default")
      (node (ref "C63") (pin "2") (pintype "passive"))
      (node (ref "R72") (pin "2") (pinfunction "2_2") (pintype "passive"))
      (node (ref "UG2") (pin "2") (pintype "passive"))
    )
    (net (code "102") (name "Net-(C80-Pad2)") (class "Default")
      (node (ref "C80") (pin "2") (pintype "passive"))
      (node (ref "R89") (pin "2") (pinfunction "2_2") (pintype "passive"))
      (node (ref "UG3") (pin "2") (pintype "passive"))
    )
    (net (code "103") (name "Net-(C82-Pad2)") (class "Default")
      (node (ref "C82") (pin "2") (pintype "passive"))
      (node (ref "R90") (pin "2") (pinfunction "2_2") (pintype "passive"))
      (node (ref "UG4") (pin "2") (pintype "passive"))
    )
    (net (code "104") (name "Net-(C97-Pad1)") (class "Default")
      (node (ref "C97") (pin "1") (pintype "passive"))
      (node (ref "R117") (pin "2") (pintype "passive"))
      (node (ref "UG5") (pin "2") (pintype "passive"))
    )
    (net (code "105") (name "Net-(C110-Pad2)") (class "Default")
      (node (ref "C110") (pin "2") (pintype "passive"))
      (node (ref "R129") (pin "2") (pinfunction "2_2") (pintype "passive"))
      (node (ref "UG6") (pin "1") (pintype "passive"))
    )
    (net (code "106") (name "Net-(D3-Pad1)") (class "Default")
      (node (ref "D3") (pin "1") (pintype "passive"))
      (node (ref "R8") (pin "1") (pintype "passive"))
    )
    (net (code "107") (name "Net-(D4-Pad1)") (class "Default")
      (node (ref "D4") (pin "1") (pintype "passive"))
      (node (ref "R9") (pin "1") (pintype "passive"))
    )
    (net (code "108") (name "Net-(D5-Pad1)") (class "Default")
      (node (ref "D5") (pin "1") (pintype "passive"))
      (node (ref "R22") (pin "1") (pintype "passive"))
    )
    (net (code "109") (name "Net-(D6-Pad1)") (class "Default")
      (node (ref "D6") (pin "1") (pintype "passive"))
      (node (ref "R23") (pin "1") (pintype "passive"))
    )
    (net (code "110") (name "Net-(D7-Pad2)") (class "Default")
      (node (ref "D7") (pin "2") (pintype "passive"))
      (node (ref "R41") (pin "1") (pinfunction "1_1") (pintype "passive"))
    )
    (net (code "111") (name "Net-(D8-Pad2)") (class "Default")
      (node (ref "D8") (pin "2") (pintype "passive"))
      (node (ref "R38") (pin "1") (pinfunction "1_1") (pintype "passive"))
    )
    (net (code "112") (name "Net-(D9-K)") (class "Default")
      (node (ref "D9") (pin "2") (pinfunction "K_2") (pintype "passive"))
      (node (ref "U3") (pin "27") (pinfunction "VBAT_27") (pintype "bidirectional"))
    )
    (net (code "113") (name "Net-(D10-Pad2)") (class "Default")
      (node (ref "D10") (pin "2") (pintype "passive"))
      (node (ref "R56") (pin "1") (pinfunction "1_1") (pintype "passive"))
    )
    (net (code "114") (name "Net-(D11-Pad2)") (class "Default")
      (node (ref "D11") (pin "2") (pintype "passive"))
      (node (ref "R51") (pin "1") (pinfunction "1_1") (pintype "passive"))
    )
    (net (code "115") (name "Net-(D12-A)") (class "Default")
      (node (ref "C49") (pin "2") (pintype "passive"))
      (node (ref "D12") (pin "1") (pinfunction "A_1") (pintype "passive"))
      (node (ref "LED2") (pin "2") (pintype "passive"))
      (node (ref "Q3") (pin "2") (pinfunction "C_2") (pintype "input"))
      (node (ref "RL1") (pin "1") (pinfunction "+_1") (pintype "passive"))
    )
    (net (code "116") (name "Net-(D15-A)") (class "Default")
      (node (ref "C52") (pin "1") (pinfunction "1_1") (pintype "passive"))
      (node (ref "D15") (pin "1") (pinfunction "A_1") (pintype "passive"))
      (node (ref "LED5") (pin "2") (pintype "passive"))
      (node (ref "Q6") (pin "2") (pinfunction "C_2") (pintype "input"))
      (node (ref "RL2") (pin "1") (pinfunction "+_1") (pintype "passive"))
    )
    (net (code "117") (name "Net-(D17-A)") (class "Default")
      (node (ref "C79") (pin "2") (pintype "passive"))
      (node (ref "D17") (pin "1") (pinfunction "A_1") (pintype "passive"))
      (node (ref "LED6") (pin "2") (pintype "passive"))
      (node (ref "Q7") (pin "2") (pinfunction "C_2") (pintype "input"))
      (node (ref "RL4") (pin "1") (pinfunction "+_1") (pintype "passive"))
    )
    (net (code "118") (name "Net-(D20-A)") (class "Default")
      (node (ref "C86") (pin "1") (pinfunction "1_1") (pintype "passive"))
      (node (ref "D20") (pin "1") (pinfunction "A_1") (pintype "passive"))
      (node (ref "LED9") (pin "2") (pintype "passive"))
      (node (ref "Q10") (pin "2") (pinfunction "C_2") (pintype "input"))
      (node (ref "RL3") (pin "1") (pinfunction "+_1") (pintype "passive"))
    )
    (net (code "119") (name "Net-(D21-A)") (class "Default")
      (node (ref "C106") (pin "1") (pinfunction "1_1") (pintype "passive"))
      (node (ref "D21") (pin "1") (pinfunction "A_1") (pintype "passive"))
      (node (ref "LED10") (pin "2") (pintype "passive"))
      (node (ref "Q11") (pin "2") (pinfunction "C_2") (pintype "input"))
      (node (ref "RL5") (pin "1") (pinfunction "+_1") (pintype "passive"))
    )
    (net (code "120") (name "Net-(D23-A)") (class "Default")
      (node (ref "D23") (pin "1") (pinfunction "A_1") (pintype "passive"))
      (node (ref "Q17") (pin "2") (pinfunction "D_2") (pintype "passive"))
    )
    (net (code "121") (name "Net-(D23-K)") (class "Default")
      (node (ref "D23") (pin "2") (pinfunction "K_2") (pintype "passive"))
      (node (ref "D24") (pin "1") (pinfunction "A_1") (pintype "passive"))
      (node (ref "D27") (pin "2") (pinfunction "K_2") (pintype "passive"))
      (node (ref "RL6") (pin "1") (pinfunction "1_1") (pintype "passive"))
    )
    (net (code "122") (name "Net-(D24-K)") (class "Default")
      (node (ref "D24") (pin "2") (pinfunction "K_2") (pintype "passive"))
      (node (ref "RL6") (pin "5") (pinfunction "5_5") (pintype "passive"))
    )
    (net (code "123") (name "Net-(DC7-Pad1)") (class "Default")
      (node (ref "DC7") (pin "1") (pinfunction "1_1") (pintype "passive"))
      (node (ref "DC8") (pin "1") (pinfunction "1_1") (pintype "passive"))
      (node (ref "RL6") (pin "4") (pinfunction "4_4") (pintype "passive"))
    )
    (net (code "124") (name "Net-(L5-Pad2)") (class "Default")
      (node (ref "L5") (pin "2") (pinfunction "2_2") (pintype "passive"))
      (node (ref "R64") (pin "1") (pintype "passive"))
      (node (ref "R75") (pin "1") (pinfunction "1_1") (pintype "passive"))
    )
    (net (code "125") (name "Net-(L7-Pad2)") (class "Default")
      (node (ref "L7") (pin "2") (pinfunction "2_2") (pintype "passive"))
      (node (ref "R87") (pin "1") (pinfunction "1_1") (pintype "passive"))
    )
    (net (code "126") (name "Net-(LED1-Pad1)") (class "Default")
      (node (ref "LED1") (pin "1") (pintype "passive"))
      (node (ref "R16") (pin "1") (pinfunction "1_1") (pintype "passive"))
    )
    (net (code "127") (name "Net-(LED2-Pad1)") (class "Default")
      (node (ref "LED2") (pin "1") (pintype "passive"))
      (node (ref "R60") (pin "1") (pinfunction "1_1") (pintype "passive"))
    )
    (net (code "128") (name "Net-(LED5-Pad1)") (class "Default")
      (node (ref "LED5") (pin "1") (pintype "passive"))
      (node (ref "R62") (pin "1") (pinfunction "1_1") (pintype "passive"))
    )
    (net (code "129") (name "Net-(LED6-Pad1)") (class "Default")
      (node (ref "LED6") (pin "1") (pintype "passive"))
      (node (ref "R93") (pin "1") (pinfunction "1_1") (pintype "passive"))
    )
    (net (code "130") (name "Net-(LED9-Pad1)") (class "Default")
      (node (ref "LED9") (pin "1") (pintype "passive"))
      (node (ref "R96") (pin "1") (pinfunction "1_1") (pintype "passive"))
    )
    (net (code "131") (name "Net-(LED10-Pad1)") (class "Default")
      (node (ref "LED10") (pin "1") (pintype "passive"))
      (node (ref "R121") (pin "1") (pinfunction "1_1") (pintype "passive"))
    )
    (net (code "132") (name "Net-(Q1-B)") (class "Default")
      (node (ref "Q1") (pin "1") (pinfunction "B_1") (pintype "input"))
      (node (ref "R29") (pin "2") (pinfunction "2_2") (pintype "passive"))
      (node (ref "R33") (pin "2") (pinfunction "2_2") (pintype "passive"))
    )
    (net (code "133") (name "Net-(Q1-C)") (class "Default")
      (node (ref "LED1") (pin "2") (pintype "passive"))
      (node (ref "Q1") (pin "2") (pinfunction "C_2") (pintype "input"))
    )
    (net (code "134") (name "Net-(Q2-B)") (class "Default")
      (node (ref "Q2") (pin "1") (pinfunction "B_1") (pintype "input"))
      (node (ref "R55") (pin "1") (pinfunction "1_1") (pintype "passive"))
      (node (ref "U11") (pin "3") (pinfunction "C_3") (pintype "passive"))
    )
    (net (code "135") (name "Net-(Q3-B)") (class "Default")
      (node (ref "C65") (pin "1") (pintype "passive"))
      (node (ref "Q3") (pin "1") (pinfunction "B_1") (pintype "input"))
      (node (ref "R77") (pin "2") (pinfunction "2_2") (pintype "passive"))
      (node (ref "R83") (pin "2") (pinfunction "2_2") (pintype "passive"))
    )
    (net (code "136") (name "Net-(Q6-B)") (class "Default")
      (node (ref "C66") (pin "2") (pinfunction "2_2") (pintype "passive"))
      (node (ref "Q6") (pin "1") (pinfunction "B_1") (pintype "input"))
      (node (ref "R80") (pin "2") (pinfunction "2_2") (pintype "passive"))
      (node (ref "R84") (pin "2") (pinfunction "2_2") (pintype "passive"))
    )
    (net (code "137") (name "Net-(Q7-B)") (class "Default")
      (node (ref "C88") (pin "1") (pintype "passive"))
      (node (ref "Q7") (pin "1") (pinfunction "B_1") (pintype "input"))
      (node (ref "R107") (pin "2") (pinfunction "2_2") (pintype "passive"))
      (node (ref "R98") (pin "2") (pinfunction "2_2") (pintype "passive"))
    )
    (net (code "138") (name "Net-(Q10-B)") (class "Default")
      (node (ref "C91") (pin "2") (pinfunction "2_2") (pintype "passive"))
      (node (ref "Q10") (pin "1") (pinfunction "B_1") (pintype "input"))
      (node (ref "R102") (pin "2") (pinfunction "2_2") (pintype "passive"))
      (node (ref "R111") (pin "2") (pinfunction "2_2") (pintype "passive"))
    )
    (net (code "139") (name "Net-(Q11-B)") (class "Default")
      (node (ref "C108") (pin "2") (pinfunction "2_2") (pintype "passive"))
      (node (ref "Q11") (pin "1") (pinfunction "B_1") (pintype "input"))
      (node (ref "R123") (pin "2") (pinfunction "2_2") (pintype "passive"))
      (node (ref "R125") (pin "2") (pinfunction "2_2") (pintype "passive"))
    )
    (net (code "140") (name "Net-(Q15-B)") (class "Default")
      (node (ref "Q15") (pin "1") (pinfunction "B_1") (pintype "input"))
      (node (ref "R133") (pin "2") (pinfunction "2_2") (pintype "passive"))
      (node (ref "R135") (pin "2") (pinfunction "2_2") (pintype "passive"))
    )
    (net (code "141") (name "Net-(Q15-C)") (class "Default")
      (node (ref "C110") (pin "1") (pintype "passive"))
      (node (ref "Q15") (pin "2") (pinfunction "C_2") (pintype "input"))
      (node (ref "UG6") (pin "2") (pintype "passive"))
    )
    (net (code "142") (name "Net-(Q17-G)") (class "Default")
      (node (ref "Q17") (pin "1") (pinfunction "G_1") (pintype "passive"))
      (node (ref "R130") (pin "2") (pinfunction "2_2") (pintype "passive"))
    )
    (net (code "143") (name "Net-(R1-Pad1)") (class "Default")
      (node (ref "R1") (pin "1") (pintype "passive"))
      (node (ref "R4") (pin "2") (pintype "passive"))
    )
    (net (code "144") (name "Net-(R10-Pad2)") (class "Default")
      (node (ref "R10") (pin "2") (pintype "passive"))
      (node (ref "TVS1") (pin "1") (pintype "passive"))
    )
    (net (code "145") (name "Net-(R24-Pad2)") (class "Default")
      (node (ref "R24") (pin "2") (pintype "passive"))
      (node (ref "TVS3") (pin "1") (pintype "passive"))
    )
    (net (code "146") (name "Net-(R65-Pad2)") (class "Default")
      (node (ref "R65") (pin "2") (pinfunction "2_2") (pintype "passive"))
      (node (ref "U12") (pin "1") (pintype "passive"))
    )
    (net (code "147") (name "Net-(R68-Pad2)") (class "Default")
      (node (ref "R68") (pin "2") (pinfunction "2_2") (pintype "passive"))
      (node (ref "R69") (pin "1") (pinfunction "1_1") (pintype "passive"))
    )
    (net (code "148") (name "Net-(R69-Pad2)") (class "Default")
      (node (ref "R69") (pin "2") (pinfunction "2_2") (pintype "passive"))
      (node (ref "R70") (pin "1") (pinfunction "1_1") (pintype "passive"))
      (node (ref "R81") (pin "2") (pinfunction "2_2") (pintype "passive"))
    )
    (net (code "149") (name "Net-(R127-Pad1)") (class "Default")
      (node (ref "R127") (pin "1") (pinfunction "1_1") (pintype "passive"))
      (node (ref "R130") (pin "1") (pinfunction "1_1") (pintype "passive"))
      (node (ref "UG6") (pin "4") (pintype "passive"))
    )
    (net (code "150") (name "Net-(SW1-COMMON)") (class "Default")
      (node (ref "C24") (pin "2") (pinfunction "2_2") (pintype "passive"))
      (node (ref "R18") (pin "1") (pinfunction "1_1") (pintype "passive"))
      (node (ref "SW1") (pin "1") (pinfunction "COMMON_1") (pintype "passive"))
      (node (ref "SW3") (pin "1") (pinfunction "1_1") (pintype "passive"))
      (node (ref "U5") (pin "1") (pinfunction "~{MR}_1") (pintype "passive"))
    )
    (net (code "151") (name "Net-(SW1-NO)") (class "Default")
      (node (ref "SW1") (pin "2") (pinfunction "NO_2") (pintype "passive"))
      (node (ref "U5") (pin "8") (pinfunction "~{WDO}_8") (pintype "passive"))
    )
    (net (code "152") (name "Net-(U1-BS)") (class "Default")
      (node (ref "C17") (pin "2") (pintype "passive"))
      (node (ref "U1") (pin "1") (pinfunction "BS_1") (pintype "passive"))
    )
    (net (code "153") (name "Net-(U1-FB)") (class "Default")
      (node (ref "R1") (pin "2") (pintype "passive"))
      (node (ref "R5") (pin "1") (pintype "passive"))
      (node (ref "U1") (pin "5") (pinfunction "FB_5") (pintype "passive"))
    )
    (net (code "154") (name "Net-(U1-comp)") (class "Default")
      (node (ref "C21") (pin "1") (pintype "passive"))
      (node (ref "U1") (pin "6") (pinfunction "comp_6") (pintype "passive"))
    )
    (net (code "155") (name "Net-(U2-Adj)") (class "Default")
      (node (ref "R3") (pin "1") (pinfunction "1_1") (pintype "passive"))
      (node (ref "R6") (pin "2") (pinfunction "2_2") (pintype "passive"))
      (node (ref "U2") (pin "5") (pinfunction "Adj_5") (pintype "passive"))
    )
    (net (code "156") (name "Net-(U2-EN)") (class "Default")
      (node (ref "R2") (pin "2") (pinfunction "2_2") (pintype "passive"))
      (node (ref "U2") (pin "1") (pinfunction "EN_1") (pintype "passive"))
    )
    (net (code "157") (name "Net-(U4-CANH{slash}485B)") (class "Default")
      (node (ref "R14") (pin "1") (pintype "passive"))
      (node (ref "U4") (pin "8") (pinfunction "CANH/485B_8") (pintype "passive"))
    )
    (net (code "158") (name "Net-(U4-CANL{slash}485A)") (class "Default")
      (node (ref "R11") (pin "1") (pintype "passive"))
      (node (ref "U4") (pin "9") (pinfunction "CANL/485A_9") (pintype "passive"))
    )
    (net (code "159") (name "Net-(U4-RG)") (class "Default")
      (node (ref "R10") (pin "1") (pintype "passive"))
      (node (ref "U4") (pin "10") (pinfunction "RG_10") (pintype "passive"))
    )
    (net (code "160") (name "Net-(U4-RXD)") (class "Default")
      (node (ref "R13") (pin "2") (pintype "passive"))
      (node (ref "U4") (pin "4") (pinfunction "RXD_4") (pintype "passive"))
    )
    (net (code "161") (name "Net-(U4-TXD)") (class "Default")
      (node (ref "R12") (pin "2") (pintype "passive"))
      (node (ref "U4") (pin "3") (pinfunction "TXD_3") (pintype "passive"))
    )
    (net (code "162") (name "Net-(U5-~{RST})") (class "Default")
      (node (ref "C27") (pin "2") (pinfunction "2_2") (pintype "passive"))
      (node (ref "R20") (pin "2") (pinfunction "2_2") (pintype "passive"))
      (node (ref "R27") (pin "1") (pinfunction "1_1") (pintype "passive"))
      (node (ref "U5") (pin "7") (pinfunction "~{RST}_7") (pintype "passive"))
    )
    (net (code "163") (name "Net-(U6-CANH{slash}485B)") (class "Default")
      (node (ref "R35") (pin "1") (pintype "passive"))
      (node (ref "U6") (pin "8") (pinfunction "CANH/485B_8") (pintype "passive"))
    )
    (net (code "164") (name "Net-(U6-CANL{slash}485A)") (class "Default")
      (node (ref "R28") (pin "1") (pintype "passive"))
      (node (ref "U6") (pin "9") (pinfunction "CANL/485A_9") (pintype "passive"))
    )
    (net (code "165") (name "Net-(U6-RG)") (class "Default")
      (node (ref "R24") (pin "1") (pintype "passive"))
      (node (ref "U6") (pin "10") (pinfunction "RG_10") (pintype "passive"))
    )
    (net (code "166") (name "Net-(U6-RXD)") (class "Default")
      (node (ref "R34") (pin "2") (pintype "passive"))
      (node (ref "U6") (pin "4") (pinfunction "RXD_4") (pintype "passive"))
    )
    (net (code "167") (name "Net-(U6-TXD)") (class "Default")
      (node (ref "R32") (pin "2") (pintype "passive"))
      (node (ref "U6") (pin "3") (pinfunction "TXD_3") (pintype "passive"))
    )
    (net (code "168") (name "Net-(U7-C-)") (class "Default")
      (node (ref "C31") (pin "1") (pintype "passive"))
      (node (ref "U7") (pin "3") (pinfunction "C-_3") (pintype "passive"))
    )
    (net (code "169") (name "Net-(U7-C1+)") (class "Default")
      (node (ref "C31") (pin "2") (pintype "passive"))
      (node (ref "U7") (pin "1") (pinfunction "C1+_1") (pintype "passive"))
    )
    (net (code "170") (name "Net-(U7-C2+)") (class "Default")
      (node (ref "C36") (pin "2") (pintype "passive"))
      (node (ref "U7") (pin "4") (pinfunction "C2+_4") (pintype "passive"))
    )
    (net (code "171") (name "Net-(U7-C2-)") (class "Default")
      (node (ref "C36") (pin "1") (pintype "passive"))
      (node (ref "U7") (pin "5") (pinfunction "C2-_5") (pintype "passive"))
    )
    (net (code "172") (name "Net-(U7-R1IN)") (class "Default")
      (node (ref "R138") (pin "1") (pintype "passive"))
      (node (ref "U7") (pin "13") (pinfunction "R1IN_13") (pintype "passive"))
    )
    (net (code "173") (name "Net-(U7-R1OUT)") (class "Default")
      (node (ref "R40") (pin "2") (pintype "passive"))
      (node (ref "U7") (pin "12") (pinfunction "R1OUT_12") (pintype "passive"))
    )
    (net (code "174") (name "Net-(U7-R2IN)") (class "Default")
      (node (ref "R37") (pin "1") (pintype "passive"))
      (node (ref "U7") (pin "8") (pinfunction "R2IN_8") (pintype "passive"))
    )
    (net (code "175") (name "Net-(U7-R2OUT)") (class "Default")
      (node (ref "R42") (pin "2") (pintype "passive"))
      (node (ref "U7") (pin "9") (pinfunction "R2OUT_9") (pintype "passive"))
    )
    (net (code "176") (name "Net-(U7-T1IN)") (class "Default")
      (node (ref "R43") (pin "2") (pintype "passive"))
      (node (ref "U7") (pin "11") (pinfunction "T1IN_11") (pintype "passive"))
    )
    (net (code "177") (name "Net-(U7-T1OUT)") (class "Default")
      (node (ref "R139") (pin "1") (pintype "passive"))
      (node (ref "U7") (pin "14") (pinfunction "T1OUT_14") (pintype "passive"))
    )
    (net (code "178") (name "Net-(U7-T2IN)") (class "Default")
      (node (ref "R44") (pin "2") (pintype "passive"))
      (node (ref "U7") (pin "10") (pinfunction "T2IN_10") (pintype "passive"))
    )
    (net (code "179") (name "Net-(U7-T2OUT)") (class "Default")
      (node (ref "R45") (pin "1") (pintype "passive"))
      (node (ref "U7") (pin "7") (pinfunction "T2OUT_7") (pintype "passive"))
    )
    (net (code "180") (name "Net-(U7-V+)") (class "Default")
      (node (ref "C32") (pin "1") (pintype "passive"))
      (node (ref "U7") (pin "2") (pinfunction "V+_2") (pintype "passive"))
    )
    (net (code "181") (name "Net-(U7-V-)") (class "Default")
      (node (ref "C37") (pin "2") (pintype "passive"))
      (node (ref "U7") (pin "6") (pinfunction "V-_6") (pintype "passive"))
    )
    (net (code "182") (name "Net-(U8-RG)") (class "Default")
      (node (ref "C30") (pin "2") (pinfunction "2_2") (pintype "passive"))
      (node (ref "R36") (pin "2") (pinfunction "2_2") (pintype "passive"))
      (node (ref "U8") (pin "8") (pinfunction "RG_8") (pintype "passive"))
    )
    (net (code "183") (name "Net-(U9-RG)") (class "Default")
      (node (ref "C38") (pin "1") (pinfunction "1_1") (pintype "passive"))
      (node (ref "R46") (pin "1") (pinfunction "1_1") (pintype "passive"))
      (node (ref "U9") (pin "8") (pinfunction "RG_8") (pintype "passive"))
    )
    (net (code "184") (name "Net-(U10-~{HOLD})") (class "Default")
      (node (ref "R47") (pin "2") (pinfunction "2_2") (pintype "passive"))
      (node (ref "U10") (pin "7") (pinfunction "~{HOLD}_7") (pintype "passive"))
    )
    (net (code "185") (name "Net-(U10-~{WP})") (class "Default")
      (node (ref "R54") (pin "2") (pinfunction "2_2") (pintype "passive"))
      (node (ref "U10") (pin "3") (pinfunction "~{WP}_3") (pintype "passive"))
    )
    (net (code "186") (name "Net-(U11-R)") (class "Default")
      (node (ref "R57") (pin "1") (pinfunction "1_1") (pintype "passive"))
      (node (ref "R58") (pin "2") (pinfunction "2_2") (pintype "passive"))
      (node (ref "U11") (pin "1") (pinfunction "R_1") (pintype "passive"))
    )
    (net (code "187") (name "Net-(U14A-OUT)") (class "Default")
      (node (ref "R65") (pin "1") (pinfunction "1_1") (pintype "passive"))
      (node (ref "U14") (pin "1") (pinfunction "OUT_1") (pintype "passive"))
    )
    (net (code "188") (name "Net-(U15A-IN-)") (class "Default")
      (node (ref "C53") (pin "2") (pinfunction "2_2") (pintype "passive"))
      (node (ref "R76") (pin "2") (pinfunction "2_2") (pintype "passive"))
      (node (ref "U12") (pin "6") (pintype "passive"))
      (node (ref "U15") (pin "2") (pinfunction "IN-_2") (pintype "passive"))
    )
    (net (code "189") (name "Net-(U15A-OUT)") (class "Default")
      (node (ref "C53") (pin "1") (pinfunction "1_1") (pintype "passive"))
      (node (ref "R76") (pin "1") (pinfunction "1_1") (pintype "passive"))
      (node (ref "R86") (pin "1") (pinfunction "1_1") (pintype "passive"))
      (node (ref "U15") (pin "1") (pinfunction "OUT_1") (pintype "passive"))
    )
    (net (code "190") (name "Net-(U17-I{slash}O1)") (class "Default")
      (node (ref "J12") (pin "2") (pinfunction "2_2") (pintype "passive"))
      (node (ref "R216") (pin "1") (pinfunction "1_1") (pintype "passive"))
      (node (ref "R218") (pin "2") (pinfunction "2_2") (pintype "passive"))
      (node (ref "U17") (pin "2") (pinfunction "I/O1_2") (pintype "passive"))
    )
    (net (code "191") (name "Net-(U17-I{slash}O2)") (class "Default")
      (node (ref "J12") (pin "3") (pinfunction "3_3") (pintype "passive"))
      (node (ref "R217") (pin "1") (pinfunction "1_1") (pintype "passive"))
      (node (ref "R219") (pin "2") (pinfunction "2_2") (pintype "passive"))
      (node (ref "U17") (pin "3") (pinfunction "I/O2_3") (pintype "passive"))
    )
    (net (code "192") (name "Net-(U17-VCC)") (class "Default")
      (node (ref "F1") (pin "2") (pinfunction "2_2") (pintype "passive"))
      (node (ref "J12") (pin "1") (pinfunction "1_1") (pintype "passive"))
      (node (ref "U17") (pin "4") (pinfunction "VCC_4") (pintype "passive"))
    )
    (net (code "193") (name "SGND") (class "Default")
      (node (ref "C77") (pin "2") (pinfunction "2_2") (pintype "passive"))
      (node (ref "D27") (pin "1") (pinfunction "A_1") (pintype "passive"))
      (node (ref "J4") (pin "2") (pinfunction "2_2") (pintype "passive"))
      (node (ref "J9") (pin "10") (pinfunction "10_10") (pintype "passive"))
      (node (ref "J9") (pin "12") (pinfunction "12_12") (pintype "passive"))
      (node (ref "J9") (pin "2") (pinfunction "2_2") (pintype "passive"))
      (node (ref "J9") (pin "4") (pinfunction "4_4") (pintype "passive"))
      (node (ref "J9") (pin "6") (pinfunction "6_6") (pintype "passive"))
      (node (ref "J9") (pin "8") (pinfunction "8_8") (pintype "passive"))
      (node (ref "L2") (pin "1") (pinfunction "1_1") (pintype "passive"))
      (node (ref "L3") (pin "1") (pinfunction "1_1") (pintype "passive"))
      (node (ref "RL6") (pin "12") (pinfunction "12_12") (pintype "passive"))
      (node (ref "RL6") (pin "3") (pinfunction "3_3") (pintype "passive"))
      (node (ref "U13") (pin "2") (pinfunction "GND_2") (pintype "passive"))
      (node (ref "UG6") (pin "3") (pintype "passive"))
    )
    (net (code "194") (name "VA3.3") (class "Default")
      (node (ref "C42") (pin "1") (pintype "passive"))
      (node (ref "C43") (pin "1") (pintype "passive"))
      (node (ref "C44") (pin "1") (pinfunction "1_1") (pintype "passive"))
      (node (ref "Q2") (pin "3") (pinfunction "E_3") (pintype "input"))
      (node (ref "R57") (pin "2") (pinfunction "2_2") (pintype "passive"))
      (node (ref "U3") (pin "14") (pinfunction "VDDA_14") (pintype "bidirectional"))
      (node (ref "U3") (pin "17") (pinfunction "VREFP_17") (pintype "bidirectional"))
    )
    (net (code "195") (name "VDD5V") (class "Default")
      (node (ref "C19") (pin "2") (pintype "passive"))
      (node (ref "C20") (pin "2") (pintype "passive"))
      (node (ref "C75") (pin "2") (pinfunction "2_2") (pintype "passive"))
      (node (ref "C76") (pin "2") (pinfunction "2_2") (pintype "passive"))
      (node (ref "DC2") (pin "1") (pinfunction "1_1") (pintype "passive"))
      (node (ref "F1") (pin "1") (pinfunction "1_1") (pintype "passive"))
      (node (ref "J6") (pin "12") (pinfunction "12_12") (pintype "passive"))
      (node (ref "L1") (pin "2") (pinfunction "2_2") (pintype "passive"))
      (node (ref "Q2") (pin "2") (pinfunction "C_2") (pintype "input"))
      (node (ref "R2") (pin "1") (pinfunction "1_1") (pintype "passive"))
      (node (ref "R4") (pin "1") (pintype "passive"))
      (node (ref "R55") (pin "2") (pinfunction "2_2") (pintype "passive"))
      (node (ref "U15") (pin "8") (pinfunction "VCC_8") (pintype "passive"))
      (node (ref "U2") (pin "2") (pinfunction "Vin_2") (pintype "passive"))
    )
    (net (code "196") (name "VDD12V") (class "Default")
      (node (ref "C106") (pin "2") (pinfunction "2_2") (pintype "passive"))
      (node (ref "C18") (pin "2") (pintype "passive"))
      (node (ref "C49") (pin "1") (pintype "passive"))
      (node (ref "C52") (pin "2") (pinfunction "2_2") (pintype "passive"))
      (node (ref "C79") (pin "1") (pintype "passive"))
      (node (ref "C86") (pin "2") (pinfunction "2_2") (pintype "passive"))
      (node (ref "D1") (pin "2") (pinfunction "K_2") (pintype "passive"))
      (node (ref "D12") (pin "2") (pinfunction "K_2") (pintype "passive"))
      (node (ref "D15") (pin "2") (pinfunction "K_2") (pintype "passive"))
      (node (ref "D17") (pin "2") (pinfunction "K_2") (pintype "passive"))
      (node (ref "D2") (pin "2") (pinfunction "K_2") (pintype "passive"))
      (node (ref "D20") (pin "2") (pinfunction "K_2") (pintype "passive"))
      (node (ref "D21") (pin "2") (pinfunction "K_2") (pintype "passive"))
      (node (ref "DC1") (pin "1") (pinfunction "1_1") (pintype "passive"))
      (node (ref "J6") (pin "8") (pinfunction "8_8") (pintype "passive"))
      (node (ref "R121") (pin "2") (pinfunction "2_2") (pintype "passive"))
      (node (ref "R60") (pin "2") (pinfunction "2_2") (pintype "passive"))
      (node (ref "R62") (pin "2") (pinfunction "2_2") (pintype "passive"))
      (node (ref "R93") (pin "2") (pinfunction "2_2") (pintype "passive"))
      (node (ref "R96") (pin "2") (pinfunction "2_2") (pintype "passive"))
      (node (ref "RL1") (pin "2") (pinfunction "-_2") (pintype "passive"))
      (node (ref "RL2") (pin "2") (pinfunction "-_2") (pintype "passive"))
      (node (ref "RL3") (pin "2") (pinfunction "-_2") (pintype "passive"))
      (node (ref "RL4") (pin "2") (pinfunction "-_2") (pintype "passive"))
      (node (ref "RL5") (pin "2") (pinfunction "-_2") (pintype "passive"))
      (node (ref "U1") (pin "2") (pinfunction "Vi_2") (pintype "passive"))
      (node (ref "U1") (pin "7") (pinfunction "EN_7") (pintype "passive"))
    )
    (net (code "197") (name "unconnected-(J12-Pad5)") (class "Default")
      (node (ref "J12") (pin "5") (pinfunction "5_5") (pintype "passive"))
    )
    (net (code "198") (name "unconnected-(MAKE1-Pad1)") (class "Default")
      (node (ref "MAKE1") (pin "1") (pinfunction "1_1") (pintype "passive"))
    )
    (net (code "199") (name "unconnected-(MARKE1-Pad1)") (class "Default")
      (node (ref "MARKE1") (pin "1") (pinfunction "1_1") (pintype "passive"))
    )
    (net (code "200") (name "unconnected-(MARKE3-Pad1)") (class "Default")
      (node (ref "MARKE3") (pin "1") (pinfunction "1_1") (pintype "passive"))
    )
    (net (code "201") (name "unconnected-(RL6-Pad8)") (class "Default")
      (node (ref "RL6") (pin "8") (pinfunction "8_8") (pintype "passive"))
    )
    (net (code "202") (name "unconnected-(RL6-Pad9)") (class "Default")
      (node (ref "RL6") (pin "9") (pinfunction "9_9") (pintype "passive"))
    )
    (net (code "203") (name "unconnected-(RL6-Pad10)") (class "Default")
      (node (ref "RL6") (pin "10") (pinfunction "10_10") (pintype "passive"))
    )
    (net (code "204") (name "unconnected-(U1-SS-Pad8)") (class "Default")
      (node (ref "U1") (pin "8") (pinfunction "SS_8") (pintype "passive"))
    )
    (net (code "205") (name "unconnected-(U3-JTAG_TDI-Pad3)") (class "Default")
      (node (ref "U3") (pin "3") (pinfunction "JTAG_TDI_3") (pintype "bidirectional"))
    )
    (net (code "206") (name "unconnected-(U3-JTAG_TRST-Pad5)") (class "Default")
      (node (ref "U3") (pin "5") (pinfunction "JTAG_TRST_5") (pintype "bidirectional"))
    )
    (net (code "207") (name "unconnected-(U3-P0[0]{slash}CAN_RD1{slash}U3_TXD{slash}I2C1_SDA{slash}U0_TXD-Pad66)") (class "Default")
      (node (ref "U3") (pin "66") (pinfunction "P0[0]/CAN_RD1/U3_TXD/I2C1_SDA/U0_TXD_66") (pintype "bidirectional"))
    )
    (net (code "208") (name "unconnected-(U3-P0[1]{slash}CAN_TD1{slash}U3_RXD{slash}I2C1_SCL{slash}U0_RXD-Pad67)") (class "Default")
      (node (ref "U3") (pin "67") (pinfunction "P0[1]/CAN_TD1/U3_RXD/I2C1_SCL/U0_RXD_67") (pintype "bidirectional"))
    )
    (net (code "209") (name "unconnected-(U3-P0[4]{slash}I2C_RX_SCK{slash}RD2{slash}T2_CAP0-Pad116)") (class "Default")
      (node (ref "U3") (pin "116") (pinfunction "P0[4]/I2C_RX_SCK/RD2/T2_CAP0_116") (pintype "bidirectional"))
    )
    (net (code "210") (name "unconnected-(U3-P0[5]{slash}I2S_RX_WS{slash}TD2{slash}T2CAP1-Pad115)") (class "Default")
      (node (ref "U3") (pin "115") (pinfunction "P0[5]/I2S_RX_WS/TD2/T2CAP1_115") (pintype "bidirectional"))
    )
    (net (code "211") (name "unconnected-(U3-P0[6]{slash}I2S_RX_SDA{slash}SSP1_SSEL{slash}T2_MAT0{slash}U1_RTS-Pad113)") (class "Default")
      (node (ref "U3") (pin "113") (pinfunction "P0[6]/I2S_RX_SDA/SSP1_SSEL/T2_MAT0/U1_RTS_113") (pintype "bidirectional"))
    )
    (net (code "212") (name "unconnected-(U3-P0[7]{slash}I2S_TX_SCK{slash}SSP1_SCK{slash}T2_MAT1{slash}RTC_EV0-Pad112)") (class "Default")
      (node (ref "U3") (pin "112") (pinfunction "P0[7]/I2S_TX_SCK/SSP1_SCK/T2_MAT1/RTC_EV0_112") (pintype "bidirectional"))
    )
    (net (code "213") (name "unconnected-(U3-P0[8]{slash}I2S_TX_WS{slash}SSP1_MISO{slash}T2_MAT2{slash}RTC_EV1-Pad111)") (class "Default")
      (node (ref "U3") (pin "111") (pinfunction "P0[8]/I2S_TX_WS/SSP1_MISO/T2_MAT2/RTC_EV1_111") (pintype "bidirectional"))
    )
    (net (code "214") (name "unconnected-(U3-P0[9]{slash}I2S_TX_SDA{slash}SSP1_MOSI{slash}T2_MAT3{slash}RTC_EV2-Pad109)") (class "Default")
      (node (ref "U3") (pin "109") (pinfunction "P0[9]/I2S_TX_SDA/SSP1_MOSI/T2_MAT3/RTC_EV2_109") (pintype "bidirectional"))
    )
    (net (code "215") (name "unconnected-(U3-P0[12]{slash}USB_PPWR2{slash}SSP1_MISO{slash}ADC0_IN6-Pad29)") (class "Default")
      (node (ref "U3") (pin "29") (pinfunction "P0[12]/USB_PPWR2/SSP1_MISO/ADC0_IN6_29") (pintype "bidirectional"))
    )
    (net (code "216") (name "unconnected-(U3-P0[13]{slash}USB_UP_LED2{slash}SSP1_MOSI{slash}ADC0_IN7-Pad32)") (class "Default")
      (node (ref "U3") (pin "32") (pinfunction "P0[13]/USB_UP_LED2/SSP1_MOSI/ADC0_IN7_32") (pintype "bidirectional"))
    )
    (net (code "217") (name "unconnected-(U3-P0[14]{slash}USB_HSTEN2{slash}SSP1_SSEL{slash}USB_CONNECT2-Pad48)") (class "Default")
      (node (ref "U3") (pin "48") (pinfunction "P0[14]/USB_HSTEN2/SSP1_SSEL/USB_CONNECT2_48") (pintype "bidirectional"))
    )
    (net (code "218") (name "unconnected-(U3-P0[19]{slash}U1_DSR{slash}SD_CLK{slash}I2C1_SDA-Pad85)") (class "Default")
      (node (ref "U3") (pin "85") (pinfunction "P0[19]/U1_DSR/SD_CLK/I2C1_SDA_85") (pintype "bidirectional"))
    )
    (net (code "219") (name "unconnected-(U3-P0[20]{slash}U1_DTR{slash}SD_CMD{slash}I2C1_SCL-Pad83)") (class "Default")
      (node (ref "U3") (pin "83") (pinfunction "P0[20]/U1_DTR/SD_CMD/I2C1_SCL_83") (pintype "bidirectional"))
    )
    (net (code "220") (name "unconnected-(U3-P0[23]{slash}AD0_IN0{slash}I2S_RX_SCK{slash}T3_CAP0-Pad13)") (class "Default")
      (node (ref "U3") (pin "13") (pinfunction "P0[23]/AD0_IN0/I2S_RX_SCK/T3_CAP0_13") (pintype "bidirectional"))
    )
    (net (code "221") (name "unconnected-(U3-P0[24]{slash}ADC0_IN1{slash}I2S_RX_WS{slash}T3_CAP1-Pad11)") (class "Default")
      (node (ref "U3") (pin "11") (pinfunction "P0[24]/ADC0_IN1/I2S_RX_WS/T3_CAP1_11") (pintype "bidirectional"))
    )
    (net (code "222") (name "unconnected-(U3-P0[25]{slash}ADC0_IN2{slash}I2S_RX_SDA{slash}U3_TXD-Pad10)") (class "Default")
      (node (ref "U3") (pin "10") (pinfunction "P0[25]/ADC0_IN2/I2S_RX_SDA/U3_TXD_10") (pintype "bidirectional"))
    )
    (net (code "223") (name "unconnected-(U3-P0[26]{slash}ADC0_IN3{slash}DAC_OUT{slash}U3_RXD-Pad8)") (class "Default")
      (node (ref "U3") (pin "8") (pinfunction "P0[26]/ADC0_IN3/DAC_OUT/U3_RXD_8") (pintype "bidirectional"))
    )
    (net (code "224") (name "unconnected-(U3-P0[28]{slash}I2C0_SCL{slash}USB_SCL1-Pad34)") (class "Default")
      (node (ref "U3") (pin "34") (pinfunction "P0[28]/I2C0_SCL/USB_SCL1_34") (pintype "bidirectional"))
    )
    (net (code "225") (name "unconnected-(U3-P1[0]{slash}ENET_TXD0{slash}T3_CAP1{slash}SSP2_SCK-Pad136)") (class "Default")
      (node (ref "U3") (pin "136") (pinfunction "P1[0]/ENET_TXD0/T3_CAP1/SSP2_SCK_136") (pintype "bidirectional"))
    )
    (net (code "226") (name "unconnected-(U3-P1[1]{slash}ENET_TXD1{slash}T3_MAT3{slash}SSP2_MOSI-Pad135)") (class "Default")
      (node (ref "U3") (pin "135") (pinfunction "P1[1]/ENET_TXD1/T3_MAT3/SSP2_MOSI_135") (pintype "bidirectional"))
    )
    (net (code "227") (name "unconnected-(U3-P1[4]{slash}ENET_TX_EN{slash}T3_MAT2{slash}SSP2_MISO-Pad133)") (class "Default")
      (node (ref "U3") (pin "133") (pinfunction "P1[4]/ENET_TX_EN/T3_MAT2/SSP2_MISO_133") (pintype "bidirectional"))
    )
    (net (code "228") (name "unconnected-(U3-P1[8]{slash}ENET_CRS{slash}T3_MAT1{slash}SSP2_SSEL-Pad132)") (class "Default")
      (node (ref "U3") (pin "132") (pinfunction "P1[8]/ENET_CRS/T3_MAT1/SSP2_SSEL_132") (pintype "bidirectional"))
    )
    (net (code "229") (name "unconnected-(U3-P1[9]{slash}ENET_RXD0{slash}T3_MAT0-Pad131)") (class "Default")
      (node (ref "U3") (pin "131") (pinfunction "P1[9]/ENET_RXD0/T3_MAT0_131") (pintype "bidirectional"))
    )
    (net (code "230") (name "unconnected-(U3-P1[10]{slash}ENET_RXD1{slash}T3_CAP0-Pad129)") (class "Default")
      (node (ref "U3") (pin "129") (pinfunction "P1[10]/ENET_RXD1/T3_CAP0_129") (pintype "bidirectional"))
    )
    (net (code "231") (name "unconnected-(U3-P1[14]{slash}ENET_RX_ER{slash}T2_CAP0-Pad128)") (class "Default")
      (node (ref "U3") (pin "128") (pinfunction "P1[14]/ENET_RX_ER/T2_CAP0_128") (pintype "bidirectional"))
    )
    (net (code "232") (name "unconnected-(U3-P1[15]{slash}ENET_RX_CLK{slash}I2C2_SDA-Pad126)") (class "Default")
      (node (ref "U3") (pin "126") (pinfunction "P1[15]/ENET_RX_CLK/I2C2_SDA_126") (pintype "bidirectional"))
    )
    (net (code "233") (name "unconnected-(U3-P1[16]{slash}ENET_MDC{slash}I2S_TX_MCLK-Pad125)") (class "Default")
      (node (ref "U3") (pin "125") (pinfunction "P1[16]/ENET_MDC/I2S_TX_MCLK_125") (pintype "bidirectional"))
    )
    (net (code "234") (name "unconnected-(U3-P1[17]{slash}ENET_MDIO{slash}I2S_RX_MCLK-Pad123)") (class "Default")
      (node (ref "U3") (pin "123") (pinfunction "P1[17]/ENET_MDIO/I2S_RX_MCLK_123") (pintype "bidirectional"))
    )
    (net (code "235") (name "unconnected-(U3-P1[20]{slash}USB_TX_DP1{slash}PWM1[2]{slash}QEI_PHA{slash}MC_FB0{slash}SSP0_SCK-Pad49)") (class "Default")
      (node (ref "U3") (pin "49") (pinfunction "P1[20]/USB_TX_DP1/PWM1[2]/QEI_PHA/MC_FB0/SSP0_SCK_49") (pintype "bidirectional"))
    )
    (net (code "236") (name "unconnected-(U3-P1[21]{slash}USB_TX_DM1{slash}PWM1[3]{slash}SSP0_SSEL{slash}MC_ABORT-Pad50)") (class "Default")
      (node (ref "U3") (pin "50") (pinfunction "P1[21]/USB_TX_DM1/PWM1[3]/SSP0_SSEL/MC_ABORT_50") (pintype "bidirectional"))
    )
    (net (code "237") (name "unconnected-(U3-P1[22]{slash}USB_RCV1{slash}USB_PWRD1{slash}T1_MAT0{slash}MC_0B{slash}_SSP1_MOSI-Pad51)") (class "Default")
      (node (ref "U3") (pin "51") (pinfunction "P1[22]/USB_RCV1/USB_PWRD1/T1_MAT0/MC_0B/_SSP1_MOSI_51") (pintype "bidirectional"))
    )
    (net (code "238") (name "unconnected-(U3-P2[2]{slash}PWM1[3]{slash}U1_CTS{slash}T2_MAT3{slash}TRACEDATA[3]-Pad105)") (class "Default")
      (node (ref "U3") (pin "105") (pinfunction "P2[2]/PWM1[3]/U1_CTS/T2_MAT3/TRACEDATA[3]_105") (pintype "bidirectional"))
    )
    (net (code "239") (name "unconnected-(U3-P2[3]{slash}PWM1[4]{slash}U1_DCD{slash}T2_MAT2{slash}TRACEDATA[2]-Pad100)") (class "Default")
      (node (ref "U3") (pin "100") (pinfunction "P2[3]/PWM1[4]/U1_DCD/T2_MAT2/TRACEDATA[2]_100") (pintype "bidirectional"))
    )
    (net (code "240") (name "unconnected-(U3-P2[4]{slash}PWM1[5]{slash}U1_DSR{slash}T2_MAT1{slash}TRACEDATA[1]-Pad99)") (class "Default")
      (node (ref "U3") (pin "99") (pinfunction "P2[4]/PWM1[5]/U1_DSR/T2_MAT1/TRACEDATA[1]_99") (pintype "bidirectional"))
    )
    (net (code "241") (name "unconnected-(U3-P2[5]{slash}PWM1[6]{slash}U1_DTR{slash}T2_MAT0{slash}TRACEDATA[0]-Pad97)") (class "Default")
      (node (ref "U3") (pin "97") (pinfunction "P2[5]/PWM1[6]/U1_DTR/T2_MAT0/TRACEDATA[0]_97") (pintype "bidirectional"))
    )
    (net (code "242") (name "unconnected-(U3-P2[9]{slash}USB_CONNECT1{slash}U2_RXD{slash}U4_RXD{slash}ENET_MDIO-Pad92)") (class "Default")
      (node (ref "U3") (pin "92") (pinfunction "P2[9]/USB_CONNECT1/U2_RXD/U4_RXD/ENET_MDIO_92") (pintype "bidirectional"))
    )
    (net (code "243") (name "unconnected-(U3-P2[13]{slash}EINT3{slash}SD_DAT[3]{slash}I2S_TX_SDA-Pad71)") (class "Default")
      (node (ref "U3") (pin "71") (pinfunction "P2[13]/EINT3/SD_DAT[3]/I2S_TX_SDA_71") (pintype "bidirectional"))
    )
    (net (code "244") (name "unconnected-(U3-P3[0]{slash}EMC_D[0]-Pad137)") (class "Default")
      (node (ref "U3") (pin "137") (pinfunction "P3[0]/EMC_D[0]_137") (pintype "bidirectional"))
    )
    (net (code "245") (name "unconnected-(U3-P3[1]{slash}EMC_D[1]-Pad140)") (class "Default")
      (node (ref "U3") (pin "140") (pinfunction "P3[1]/EMC_D[1]_140") (pintype "bidirectional"))
    )
    (net (code "246") (name "unconnected-(U3-P3[2]{slash}EMC_D[2]-Pad144)") (class "Default")
      (node (ref "U3") (pin "144") (pinfunction "P3[2]/EMC_D[2]_144") (pintype "bidirectional"))
    )
    (net (code "247") (name "unconnected-(U3-P3[3]{slash}EMC_D[3]-Pad2)") (class "Default")
      (node (ref "U3") (pin "2") (pinfunction "P3[3]/EMC_D[3]_2") (pintype "bidirectional"))
    )
    (net (code "248") (name "unconnected-(U3-P3[4]{slash}EMC_D[4]-Pad9)") (class "Default")
      (node (ref "U3") (pin "9") (pinfunction "P3[4]/EMC_D[4]_9") (pintype "bidirectional"))
    )
    (net (code "249") (name "unconnected-(U3-P3[5]{slash}EMC_D[5]-Pad12)") (class "Default")
      (node (ref "U3") (pin "12") (pinfunction "P3[5]/EMC_D[5]_12") (pintype "bidirectional"))
    )
    (net (code "250") (name "unconnected-(U3-P3[6]{slash}EMC_D[6]-Pad16)") (class "Default")
      (node (ref "U3") (pin "16") (pinfunction "P3[6]/EMC_D[6]_16") (pintype "bidirectional"))
    )
    (net (code "251") (name "unconnected-(U3-P3[7]{slash}EMC_D[7]-Pad19)") (class "Default")
      (node (ref "U3") (pin "19") (pinfunction "P3[7]/EMC_D[7]_19") (pintype "bidirectional"))
    )
    (net (code "252") (name "unconnected-(U3-P3[23]{slash}EMC_D[23]{slash}PWM1_CAP0{slash}T0_CAP0-Pad45)") (class "Default")
      (node (ref "U3") (pin "45") (pinfunction "P3[23]/EMC_D[23]/PWM1_CAP0/T0_CAP0_45") (pintype "bidirectional"))
    )
    (net (code "253") (name "unconnected-(U3-P4[0]{slash}EMC_A[0]-Pad52)") (class "Default")
      (node (ref "U3") (pin "52") (pinfunction "P4[0]/EMC_A[0]_52") (pintype "bidirectional"))
    )
    (net (code "254") (name "unconnected-(U3-P4[1]{slash}EMC_A[1]-Pad55)") (class "Default")
      (node (ref "U3") (pin "55") (pinfunction "P4[1]/EMC_A[1]_55") (pintype "bidirectional"))
    )
    (net (code "255") (name "unconnected-(U3-P4[2]{slash}EMC_A[2]-Pad58)") (class "Default")
      (node (ref "U3") (pin "58") (pinfunction "P4[2]/EMC_A[2]_58") (pintype "bidirectional"))
    )
    (net (code "256") (name "unconnected-(U3-P4[3]{slash}EMC_A[3]-Pad68)") (class "Default")
      (node (ref "U3") (pin "68") (pinfunction "P4[3]/EMC_A[3]_68") (pintype "bidirectional"))
    )
    (net (code "257") (name "unconnected-(U3-P4[5]{slash}EMC_A[5]-Pad74)") (class "Default")
      (node (ref "U3") (pin "74") (pinfunction "P4[5]/EMC_A[5]_74") (pintype "bidirectional"))
    )
    (net (code "258") (name "unconnected-(U3-P4[6]{slash}EMC_A[6]-Pad78)") (class "Default")
      (node (ref "U3") (pin "78") (pinfunction "P4[6]/EMC_A[6]_78") (pintype "bidirectional"))
    )
    (net (code "259") (name "unconnected-(U3-P4[7]{slash}EMC_A[7]-Pad84)") (class "Default")
      (node (ref "U3") (pin "84") (pinfunction "P4[7]/EMC_A[7]_84") (pintype "bidirectional"))
    )
    (net (code "260") (name "unconnected-(U3-P4[8]{slash}EMC_A[8]-Pad88)") (class "Default")
      (node (ref "U3") (pin "88") (pinfunction "P4[8]/EMC_A[8]_88") (pintype "bidirectional"))
    )
    (net (code "261") (name "unconnected-(U3-P4[9]{slash}EMC_A[9]-Pad91)") (class "Default")
      (node (ref "U3") (pin "91") (pinfunction "P4[9]/EMC_A[9]_91") (pintype "bidirectional"))
    )
    (net (code "262") (name "unconnected-(U3-P4[10]{slash}EMC_A[10]-Pad94)") (class "Default")
      (node (ref "U3") (pin "94") (pinfunction "P4[10]/EMC_A[10]_94") (pintype "bidirectional"))
    )
    (net (code "263") (name "unconnected-(U3-P4[11]{slash}EMC_A[11]-Pad101)") (class "Default")
      (node (ref "U3") (pin "101") (pinfunction "P4[11]/EMC_A[11]_101") (pintype "bidirectional"))
    )
    (net (code "264") (name "unconnected-(U3-P4[12]{slash}EMC_A[12]-Pad104)") (class "Default")
      (node (ref "U3") (pin "104") (pinfunction "P4[12]/EMC_A[12]_104") (pintype "bidirectional"))
    )
    (net (code "265") (name "unconnected-(U3-P4[13]{slash}EMC_A[13]-Pad108)") (class "Default")
      (node (ref "U3") (pin "108") (pinfunction "P4[13]/EMC_A[13]_108") (pintype "bidirectional"))
    )
    (net (code "266") (name "unconnected-(U3-P4[14]{slash}EMC_A[14]-Pad110)") (class "Default")
      (node (ref "U3") (pin "110") (pinfunction "P4[14]/EMC_A[14]_110") (pintype "bidirectional"))
    )
    (net (code "267") (name "unconnected-(U3-P4[15]{slash}EMC_A[15]-Pad120)") (class "Default")
      (node (ref "U3") (pin "120") (pinfunction "P4[15]/EMC_A[15]_120") (pintype "bidirectional"))
    )
    (net (code "268") (name "unconnected-(U3-P4[24]{slash}EMC_OE-Pad127)") (class "Default")
      (node (ref "U3") (pin "127") (pinfunction "P4[24]/EMC_OE_127") (pintype "bidirectional"))
    )
    (net (code "269") (name "unconnected-(U3-P4[25]{slash}EMC_WE-Pad124)") (class "Default")
      (node (ref "U3") (pin "124") (pinfunction "P4[25]/EMC_WE_124") (pintype "bidirectional"))
    )
    (net (code "270") (name "unconnected-(U3-P5[0]{slash}EMC_A[24]{slash}SSP2_MOSI{slash}T2_MAT2-Pad6)") (class "Default")
      (node (ref "U3") (pin "6") (pinfunction "P5[0]/EMC_A[24]/SSP2_MOSI/T2_MAT2_6") (pintype "bidirectional"))
    )
    (net (code "271") (name "unconnected-(U3-P5[1]{slash}EMC_BLS3{slash}U3_RXD{slash}T2_MAT1{slash}I2C2_SCL-Pad21)") (class "Default")
      (node (ref "U3") (pin "21") (pinfunction "P5[1]/EMC_BLS3/U3_RXD/T2_MAT1/I2C2_SCL_21") (pintype "bidirectional"))
    )
    (net (code "272") (name "unconnected-(U3-P5[2]{slash}T3_MAT2{slash}I2C0{slash}SDA-Pad81)") (class "Default")
      (node (ref "U3") (pin "81") (pinfunction "P5[2]/T3_MAT2/I2C0/SDA_81") (pintype "bidirectional"))
    )
    (net (code "273") (name "unconnected-(U3-RSTOUT-Pad20)") (class "Default")
      (node (ref "U3") (pin "20") (pinfunction "RSTOUT_20") (pintype "bidirectional"))
    )
    (net (code "274") (name "unconnected-(U3-RTC_ALARM-Pad26)") (class "Default")
      (node (ref "U3") (pin "26") (pinfunction "RTC_ALARM_26") (pintype "bidirectional"))
    )
    (net (code "275") (name "unconnected-(U5-~{PFO}-Pad5)") (class "Default")
      (node (ref "U5") (pin "5") (pinfunction "~{PFO}_5") (pintype "passive+no_connect"))
    )
    (net (code "276") (name "unconnected-(U15B-IN+-Pad5)") (class "Default")
      (node (ref "U15") (pin "5") (pinfunction "IN+_5") (pintype "passive"))
    )
    (net (code "277") (name "unconnected-(U15B-IN--Pad6)") (class "Default")
      (node (ref "U15") (pin "6") (pinfunction "IN-_6") (pintype "passive"))
    )
    (net (code "278") (name "unconnected-(U15B-OUT-Pad7)") (class "Default")
      (node (ref "U15") (pin "7") (pinfunction "OUT_7") (pintype "passive"))
    )
  )
)
